# homeboard22.net
KiCad netlist of a schematic drawn in EAGLE
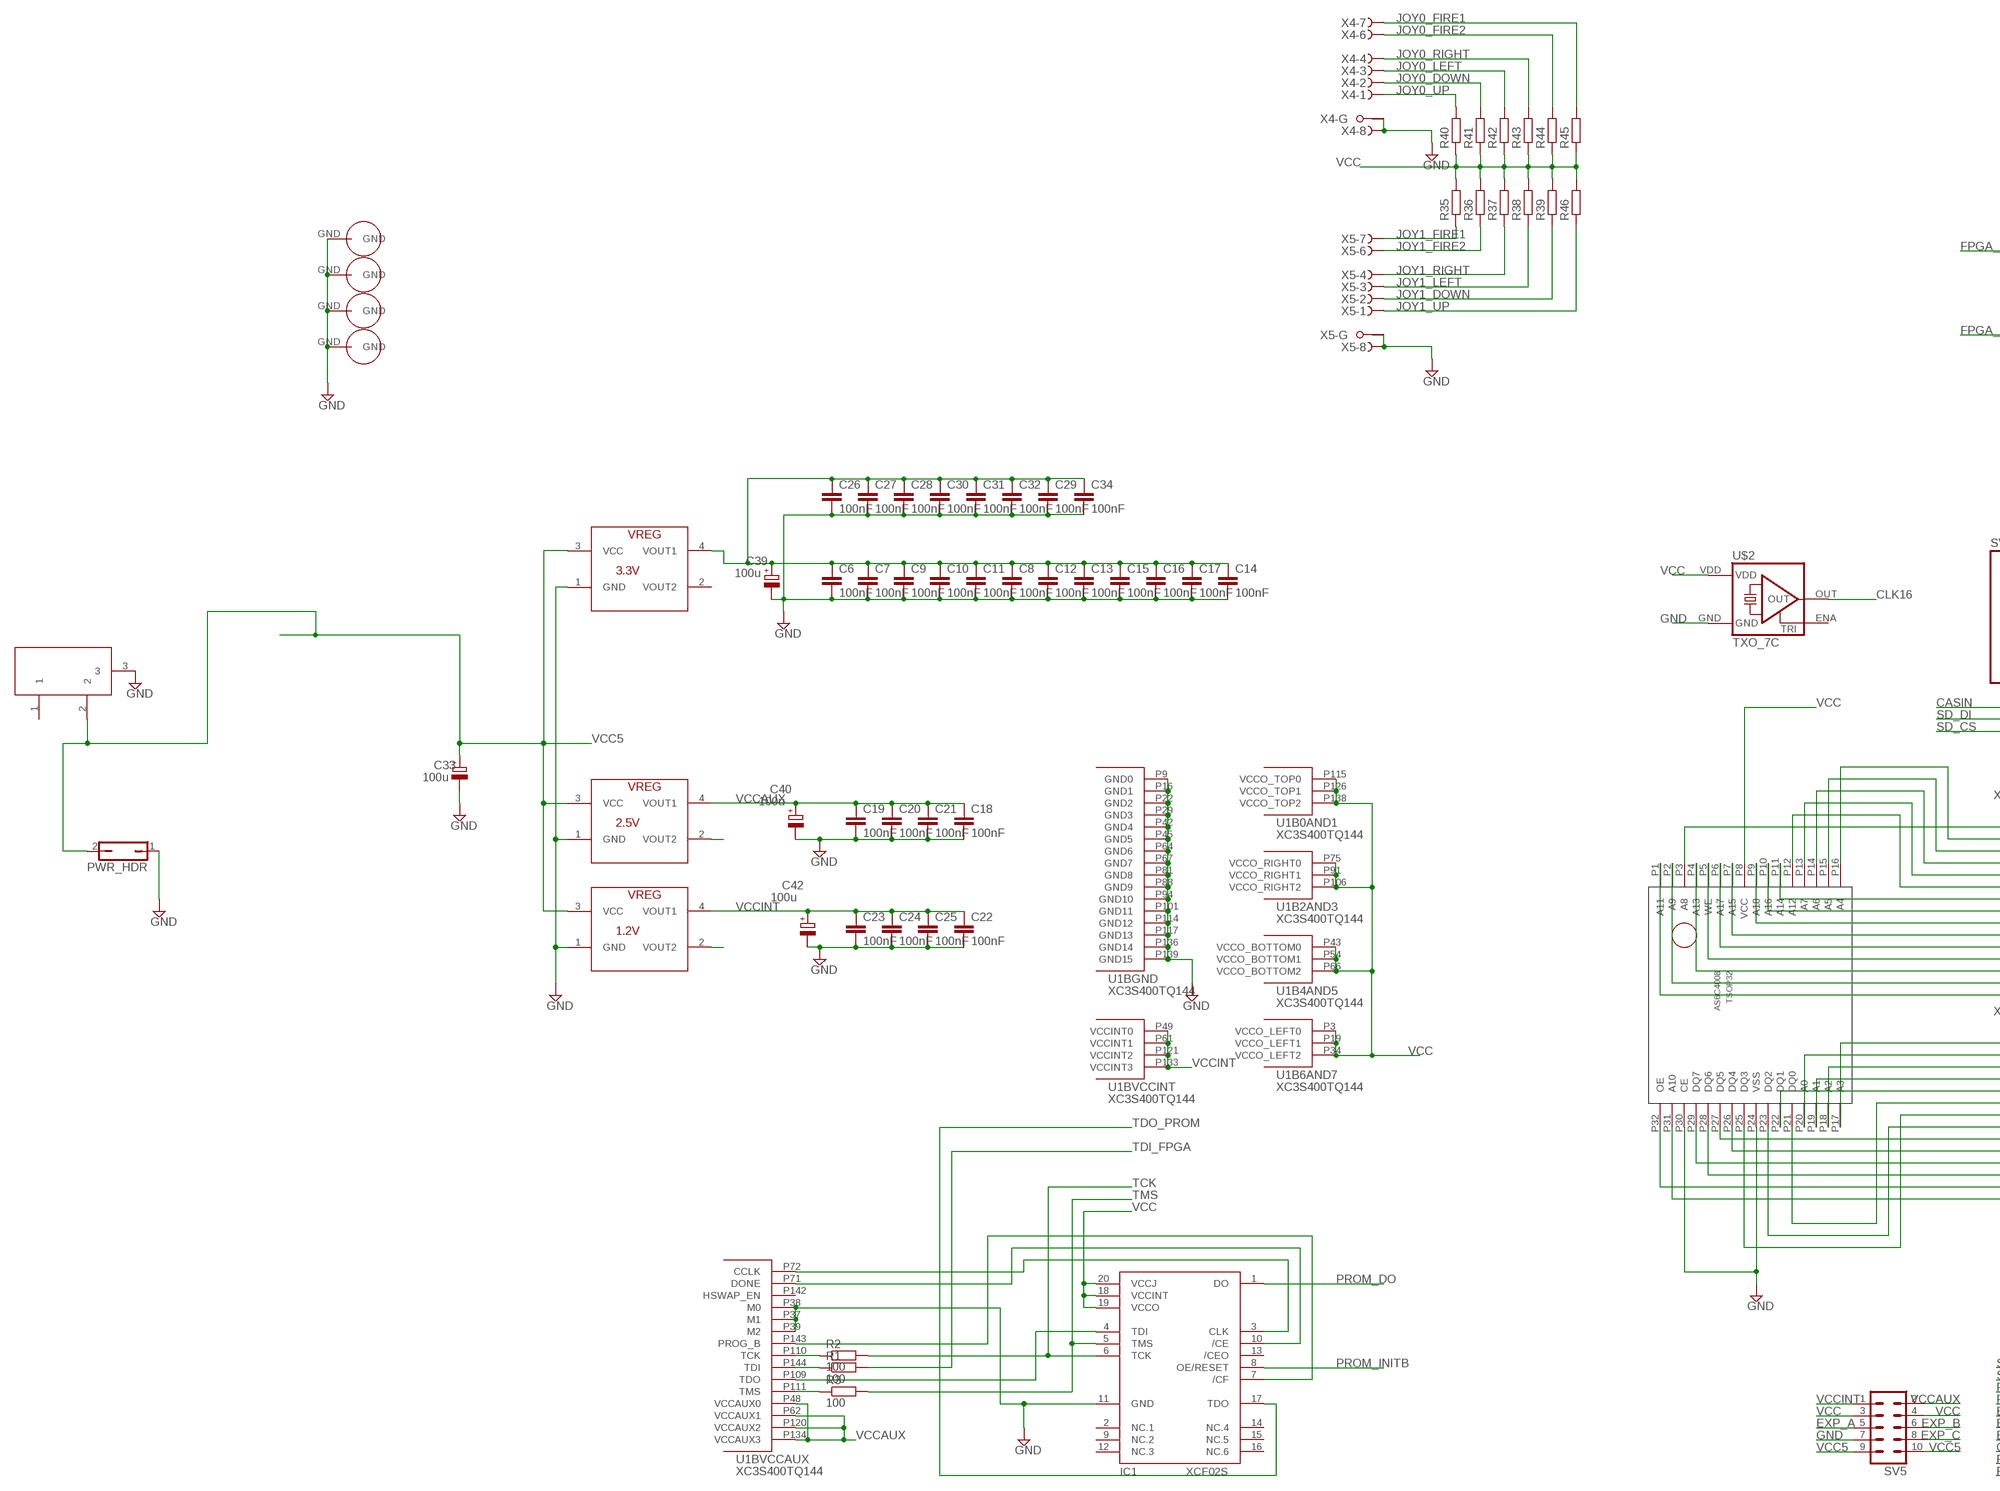
[diagram p0: schematic, sheet 1, part 1 of 3]
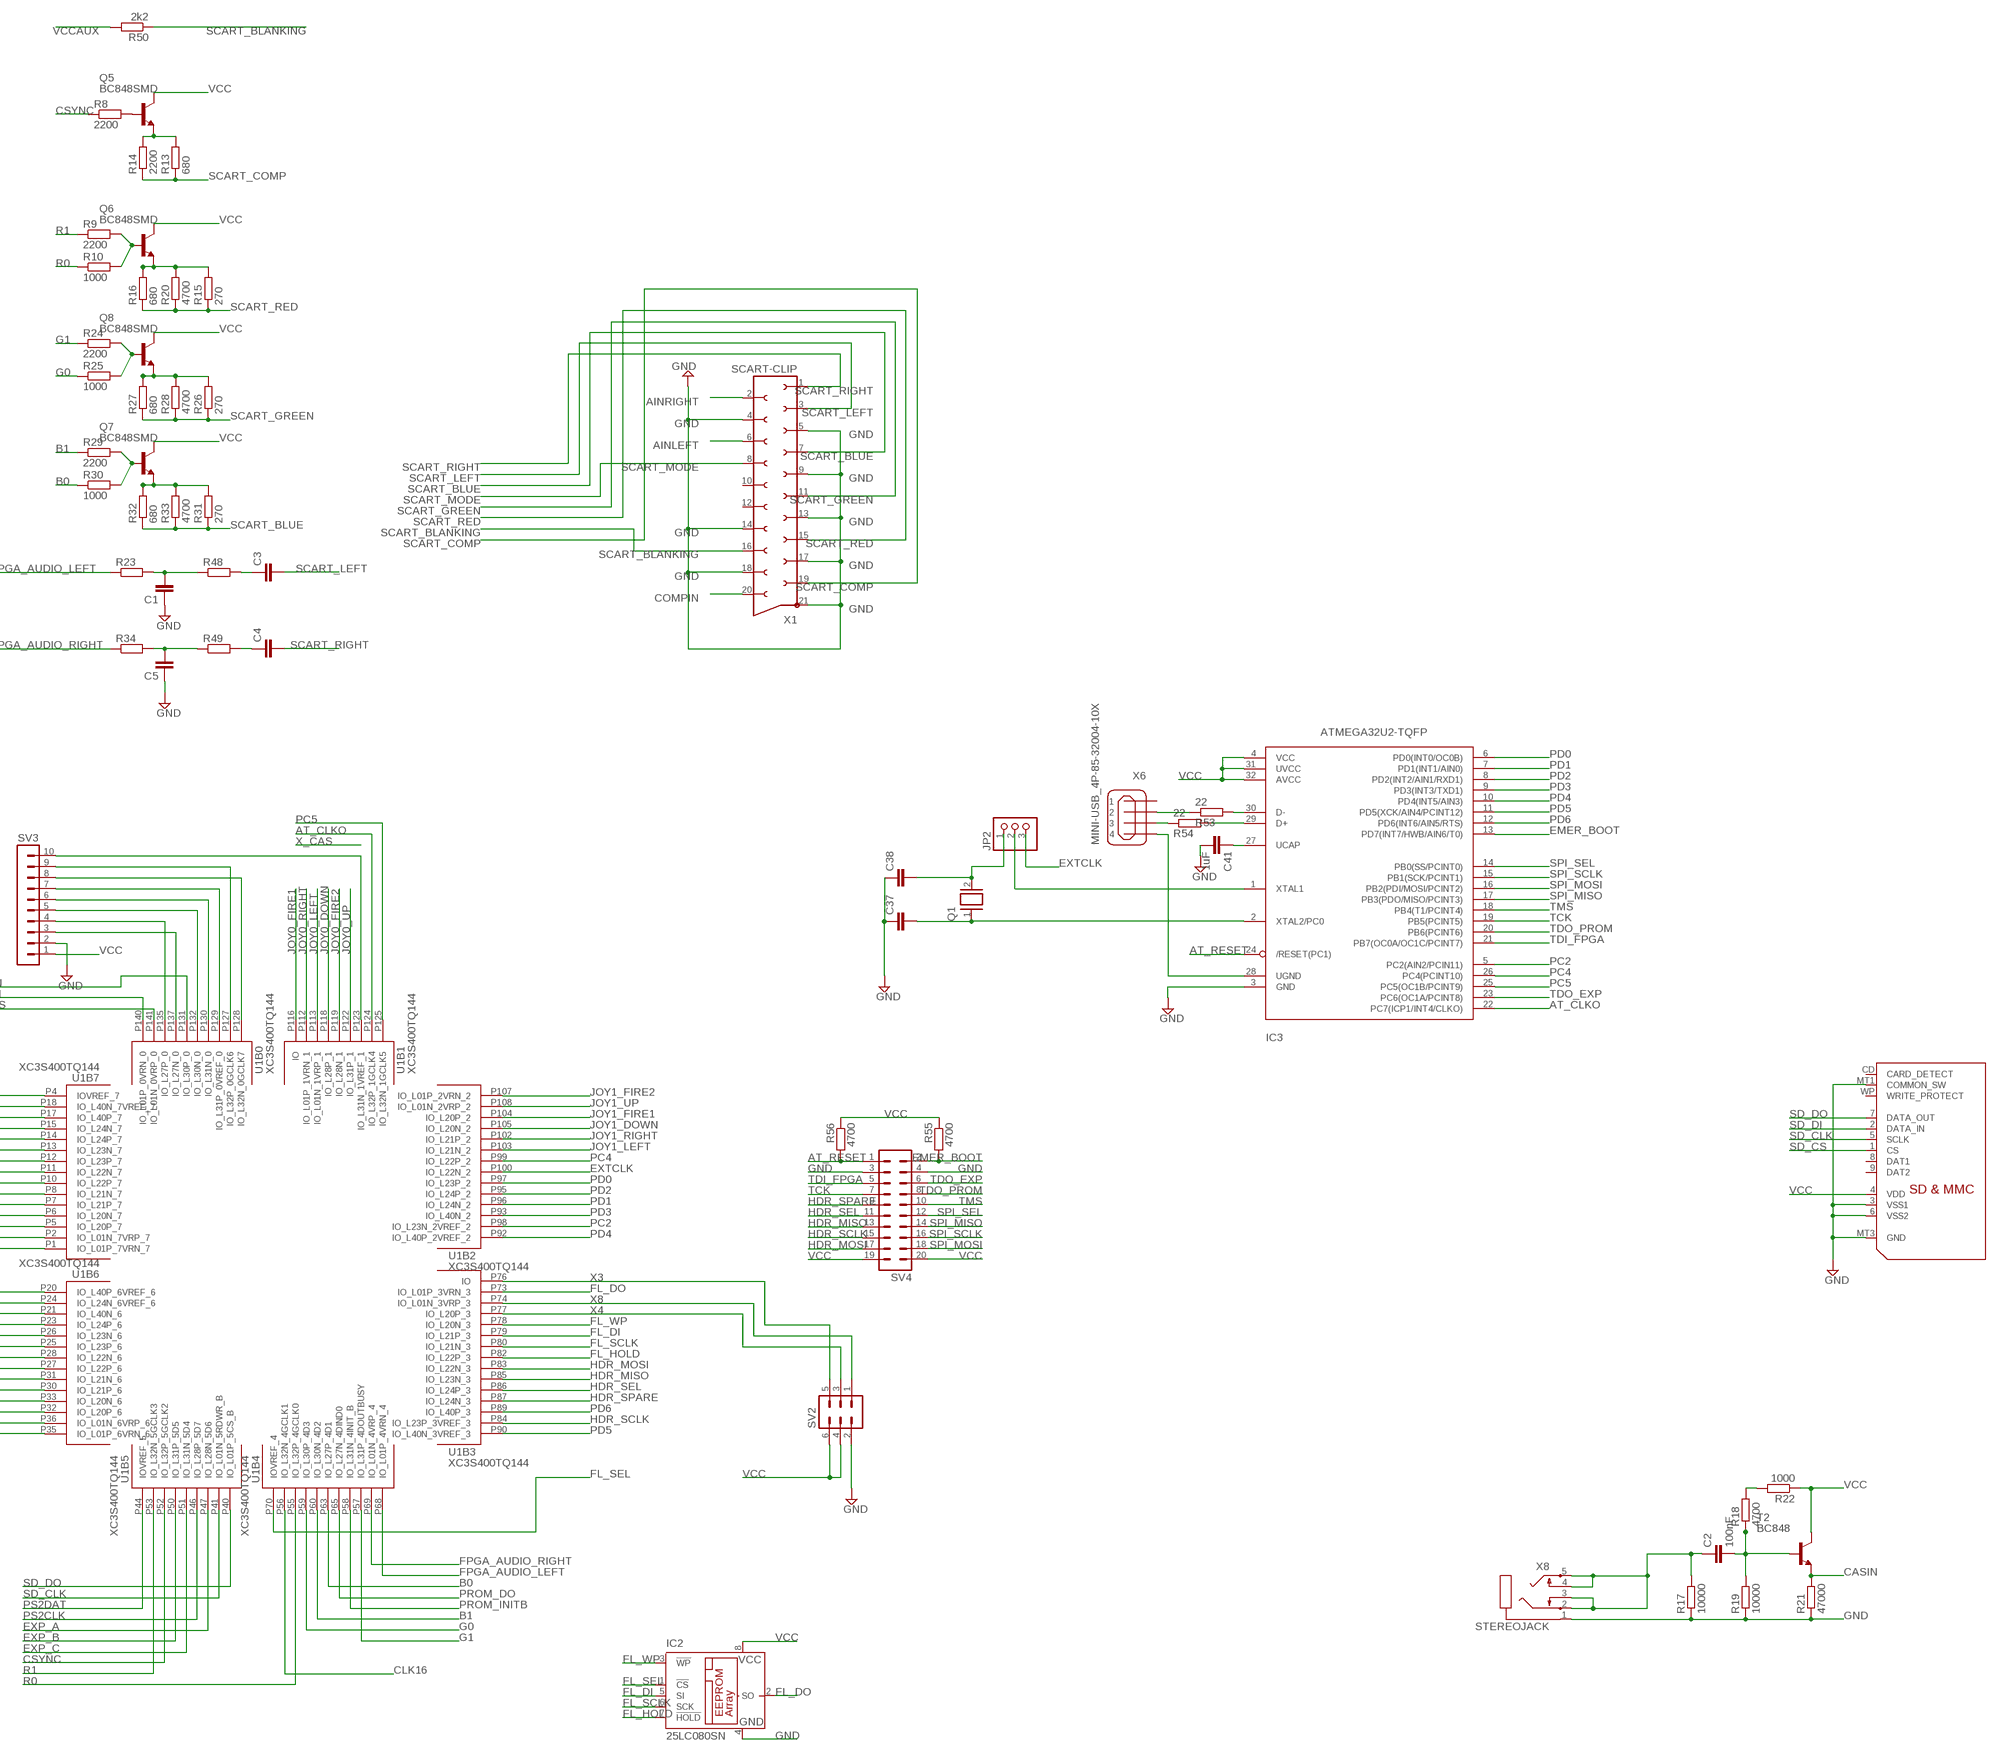
[diagram p1: schematic, sheet 1, part 2 of 3]
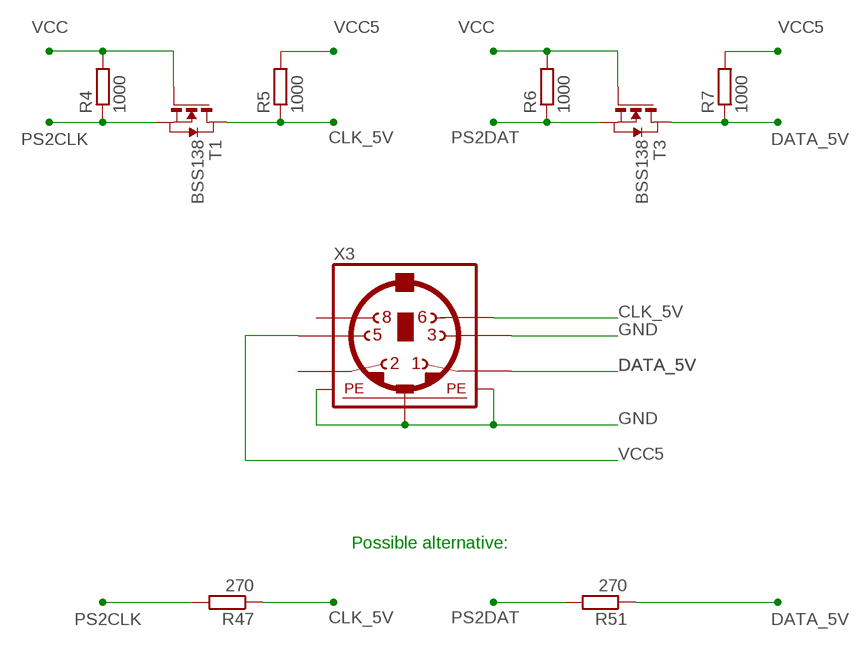
[diagram p2: schematic, sheet 1, part 3 of 3]

(export (version "E")
  (design (tool "Eeschema 10.0.6"))
  (components
    (comp (ref "C1")
      (value "C-EUC0603")
      (footprint "eagle-import:C0603")
      (libsource (lib "eagle-import") (part "resistor_C-EUC0603"))
    )
    (comp (ref "C2")
      (value "100nF")
      (footprint "eagle-import:C0603")
      (libsource (lib "eagle-import") (part "resistor_C-EUC0603"))
    )
    (comp (ref "C3")
      (value "C-EUC0603")
      (footprint "eagle-import:C0603")
      (libsource (lib "eagle-import") (part "resistor_C-EUC0603"))
    )
    (comp (ref "C4")
      (value "C-EUC0603")
      (footprint "eagle-import:C0603")
      (libsource (lib "eagle-import") (part "resistor_C-EUC0603"))
    )
    (comp (ref "C5")
      (value "C-EUC0603")
      (footprint "eagle-import:C0603")
      (libsource (lib "eagle-import") (part "resistor_C-EUC0603"))
    )
    (comp (ref "C6")
      (value "100nF")
      (footprint "eagle-import:C0603")
      (libsource (lib "eagle-import") (part "C-EUC0603"))
    )
    (comp (ref "C7")
      (value "100nF")
      (footprint "eagle-import:C0603")
      (libsource (lib "eagle-import") (part "C-EUC0603"))
    )
    (comp (ref "C8")
      (value "100nF")
      (footprint "eagle-import:C0603")
      (libsource (lib "eagle-import") (part "C-EUC0603"))
    )
    (comp (ref "C9")
      (value "100nF")
      (footprint "eagle-import:C0603")
      (libsource (lib "eagle-import") (part "C-EUC0603"))
    )
    (comp (ref "C10")
      (value "100nF")
      (footprint "eagle-import:C0603")
      (libsource (lib "eagle-import") (part "C-EUC0603"))
    )
    (comp (ref "C11")
      (value "100nF")
      (footprint "eagle-import:C0603")
      (libsource (lib "eagle-import") (part "C-EUC0603"))
    )
    (comp (ref "C12")
      (value "100nF")
      (footprint "eagle-import:C0603")
      (libsource (lib "eagle-import") (part "C-EUC0603"))
    )
    (comp (ref "C13")
      (value "100nF")
      (footprint "eagle-import:C0603")
      (libsource (lib "eagle-import") (part "C-EUC0603"))
    )
    (comp (ref "C14")
      (value "100nF")
      (footprint "eagle-import:C0603")
      (libsource (lib "eagle-import") (part "C-EUC0603"))
    )
    (comp (ref "C15")
      (value "100nF")
      (footprint "eagle-import:C0603")
      (libsource (lib "eagle-import") (part "C-EUC0603"))
    )
    (comp (ref "C16")
      (value "100nF")
      (footprint "eagle-import:C0603")
      (libsource (lib "eagle-import") (part "C-EUC0603"))
    )
    (comp (ref "C17")
      (value "100nF")
      (footprint "eagle-import:C0603")
      (libsource (lib "eagle-import") (part "C-EUC0603"))
    )
    (comp (ref "C18")
      (value "100nF")
      (footprint "eagle-import:C0603")
      (libsource (lib "eagle-import") (part "C-EUC0603"))
    )
    (comp (ref "C19")
      (value "100nF")
      (footprint "eagle-import:C0603")
      (libsource (lib "eagle-import") (part "C-EUC0603"))
    )
    (comp (ref "C20")
      (value "100nF")
      (footprint "eagle-import:C0603")
      (libsource (lib "eagle-import") (part "C-EUC0603"))
    )
    (comp (ref "C21")
      (value "100nF")
      (footprint "eagle-import:C0603")
      (libsource (lib "eagle-import") (part "C-EUC0603"))
    )
    (comp (ref "C22")
      (value "100nF")
      (footprint "eagle-import:C0603")
      (libsource (lib "eagle-import") (part "C-EUC0603"))
    )
    (comp (ref "C23")
      (value "100nF")
      (footprint "eagle-import:C0603")
      (libsource (lib "eagle-import") (part "C-EUC0603"))
    )
    (comp (ref "C24")
      (value "100nF")
      (footprint "eagle-import:C0603")
      (libsource (lib "eagle-import") (part "C-EUC0603"))
    )
    (comp (ref "C25")
      (value "100nF")
      (footprint "eagle-import:C0603")
      (libsource (lib "eagle-import") (part "C-EUC0603"))
    )
    (comp (ref "C26")
      (value "100nF")
      (footprint "eagle-import:C0603")
      (libsource (lib "eagle-import") (part "C-EUC0603"))
    )
    (comp (ref "C27")
      (value "100nF")
      (footprint "eagle-import:C0603")
      (libsource (lib "eagle-import") (part "C-EUC0603"))
    )
    (comp (ref "C28")
      (value "100nF")
      (footprint "eagle-import:C0603")
      (libsource (lib "eagle-import") (part "C-EUC0603"))
    )
    (comp (ref "C29")
      (value "100nF")
      (footprint "eagle-import:C0603")
      (libsource (lib "eagle-import") (part "C-EUC0603"))
    )
    (comp (ref "C30")
      (value "100nF")
      (footprint "eagle-import:C0603")
      (libsource (lib "eagle-import") (part "C-EUC0603"))
    )
    (comp (ref "C31")
      (value "100nF")
      (footprint "eagle-import:C0603")
      (libsource (lib "eagle-import") (part "C-EUC0603"))
    )
    (comp (ref "C32")
      (value "100nF")
      (footprint "eagle-import:C0603")
      (libsource (lib "eagle-import") (part "C-EUC0603"))
    )
    (comp (ref "C33")
      (value "100u")
      (footprint "eagle-import:PANASONIC_D")
      (libsource (lib "eagle-import") (part "CPOL-EUD"))
    )
    (comp (ref "C34")
      (value "100nF")
      (footprint "eagle-import:C0603")
      (libsource (lib "eagle-import") (part "C-EUC0603"))
    )
    (comp (ref "C37")
      (value "C-EUC0805")
      (footprint "eagle-import:C0805")
      (libsource (lib "eagle-import") (part "C-EUC0805"))
    )
    (comp (ref "C38")
      (value "C-EUC0805")
      (footprint "eagle-import:C0805")
      (libsource (lib "eagle-import") (part "C-EUC0805"))
    )
    (comp (ref "C39")
      (value "100u")
      (footprint "eagle-import:PANASONIC_D")
      (libsource (lib "eagle-import") (part "CPOL-EUD"))
    )
    (comp (ref "C40")
      (value "100u")
      (footprint "eagle-import:PANASONIC_D")
      (libsource (lib "eagle-import") (part "CPOL-EUD"))
    )
    (comp (ref "C41")
      (value "1uF")
      (footprint "eagle-import:C0805")
      (libsource (lib "eagle-import") (part "C-EUC0805"))
    )
    (comp (ref "C42")
      (value "100u")
      (footprint "eagle-import:PANASONIC_D")
      (libsource (lib "eagle-import") (part "CPOL-EUD"))
    )
    (comp (ref "IC1")
      (value "XCF02S")
      (footprint "eagle-import:VO20")
      (libsource (lib "eagle-import") (part "XCF02S"))
    )
    (comp (ref "IC2")
      (value "25LC080SN")
      (footprint "eagle-import:SO-08")
      (fields (field (name "MF") "MICROCHIP") (field (name "MPN") "25LC080/SN"))
      (libsource (lib "eagle-import") (part "25SNLC080"))
    )
    (comp (ref "IC3")
      (value "ATMEGA32U2-TQFP")
      (footprint "eagle-import:TQFP32-08")
      (libsource (lib "eagle-import") (part "ATMEGA32U2-TQFP"))
    )
    (comp (ref "JP2")
      (value "PINHD-1X3")
      (footprint "eagle-import:1X03")
      (libsource (lib "eagle-import") (part "PINHD-1X3"))
    )
    (comp (ref "PWR_HDR")
      (value "JP1Q")
      (footprint "eagle-import:JP1")
      (libsource (lib "eagle-import") (part "JP1Q"))
    )
    (comp (ref "Q1")
      (value "XTAL/S")
      (footprint "eagle-import:QS")
      (libsource (lib "eagle-import") (part "XTAL/S"))
    )
    (comp (ref "Q5")
      (value "BC848SMD")
      (footprint "eagle-import:SOT23")
      (libsource (lib "eagle-import") (part "BC848SMD"))
    )
    (comp (ref "Q6")
      (value "BC848SMD")
      (footprint "eagle-import:SOT23")
      (libsource (lib "eagle-import") (part "BC848SMD"))
    )
    (comp (ref "Q7")
      (value "BC848SMD")
      (footprint "eagle-import:SOT23")
      (libsource (lib "eagle-import") (part "BC848SMD"))
    )
    (comp (ref "Q8")
      (value "BC848SMD")
      (footprint "eagle-import:SOT23")
      (libsource (lib "eagle-import") (part "BC848SMD"))
    )
    (comp (ref "R1")
      (value "100")
      (footprint "eagle-import:R0805")
      (libsource (lib "eagle-import") (part "R-EU_R0805"))
    )
    (comp (ref "R2")
      (value "100")
      (footprint "eagle-import:R0805")
      (libsource (lib "eagle-import") (part "R-EU_R0805"))
    )
    (comp (ref "R3")
      (value "100")
      (footprint "eagle-import:R0805")
      (libsource (lib "eagle-import") (part "R-EU_R0805"))
    )
    (comp (ref "R4")
      (value "1000")
      (footprint "eagle-import:R0805")
      (libsource (lib "eagle-import") (part "R-EU_R0805"))
    )
    (comp (ref "R5")
      (value "1000")
      (footprint "eagle-import:R0805")
      (libsource (lib "eagle-import") (part "R-EU_R0805"))
    )
    (comp (ref "R6")
      (value "1000")
      (footprint "eagle-import:R0805")
      (libsource (lib "eagle-import") (part "R-EU_R0805"))
    )
    (comp (ref "R7")
      (value "1000")
      (footprint "eagle-import:R0805")
      (libsource (lib "eagle-import") (part "R-EU_R0805"))
    )
    (comp (ref "R8")
      (value "2200")
      (footprint "eagle-import:R0805")
      (libsource (lib "eagle-import") (part "R-EU_R0805"))
    )
    (comp (ref "R9")
      (value "2200")
      (footprint "eagle-import:R0805")
      (libsource (lib "eagle-import") (part "R-EU_R0805"))
    )
    (comp (ref "R10")
      (value "1000")
      (footprint "eagle-import:R0805")
      (libsource (lib "eagle-import") (part "R-EU_R0805"))
    )
    (comp (ref "R13")
      (value "680")
      (footprint "eagle-import:R0805")
      (libsource (lib "eagle-import") (part "R-EU_R0805"))
    )
    (comp (ref "R14")
      (value "2200")
      (footprint "eagle-import:R0805")
      (libsource (lib "eagle-import") (part "R-EU_R0805"))
    )
    (comp (ref "R15")
      (value "270")
      (footprint "eagle-import:R0805")
      (libsource (lib "eagle-import") (part "R-EU_R0805"))
    )
    (comp (ref "R16")
      (value "680")
      (footprint "eagle-import:R0805")
      (libsource (lib "eagle-import") (part "R-EU_R0805"))
    )
    (comp (ref "R17")
      (value "10000")
      (footprint "eagle-import:R0805")
      (libsource (lib "eagle-import") (part "R-EU_R0805"))
    )
    (comp (ref "R18")
      (value "4700")
      (footprint "eagle-import:R0805")
      (libsource (lib "eagle-import") (part "R-EU_R0805"))
    )
    (comp (ref "R19")
      (value "10000")
      (footprint "eagle-import:R0805")
      (libsource (lib "eagle-import") (part "R-EU_R0805"))
    )
    (comp (ref "R20")
      (value "4700")
      (footprint "eagle-import:R0805")
      (libsource (lib "eagle-import") (part "R-EU_R0805"))
    )
    (comp (ref "R21")
      (value "47000")
      (footprint "eagle-import:R0805")
      (libsource (lib "eagle-import") (part "R-EU_R0805"))
    )
    (comp (ref "R22")
      (value "1000")
      (footprint "eagle-import:R0805")
      (libsource (lib "eagle-import") (part "R-EU_R0805"))
    )
    (comp (ref "R23")
      (value "R-EU_M0805")
      (footprint "eagle-import:M0805")
      (libsource (lib "eagle-import") (part "resistor_R-EU_M0805"))
    )
    (comp (ref "R24")
      (value "2200")
      (footprint "eagle-import:R0805")
      (libsource (lib "eagle-import") (part "R-EU_R0805"))
    )
    (comp (ref "R25")
      (value "1000")
      (footprint "eagle-import:R0805")
      (libsource (lib "eagle-import") (part "R-EU_R0805"))
    )
    (comp (ref "R26")
      (value "270")
      (footprint "eagle-import:R0805")
      (libsource (lib "eagle-import") (part "R-EU_R0805"))
    )
    (comp (ref "R27")
      (value "680")
      (footprint "eagle-import:R0805")
      (libsource (lib "eagle-import") (part "R-EU_R0805"))
    )
    (comp (ref "R28")
      (value "4700")
      (footprint "eagle-import:R0805")
      (libsource (lib "eagle-import") (part "R-EU_R0805"))
    )
    (comp (ref "R29")
      (value "2200")
      (footprint "eagle-import:R0805")
      (libsource (lib "eagle-import") (part "R-EU_R0805"))
    )
    (comp (ref "R30")
      (value "1000")
      (footprint "eagle-import:R0805")
      (libsource (lib "eagle-import") (part "R-EU_R0805"))
    )
    (comp (ref "R31")
      (value "270")
      (footprint "eagle-import:R0805")
      (libsource (lib "eagle-import") (part "R-EU_R0805"))
    )
    (comp (ref "R32")
      (value "680")
      (footprint "eagle-import:R0805")
      (libsource (lib "eagle-import") (part "R-EU_R0805"))
    )
    (comp (ref "R33")
      (value "4700")
      (footprint "eagle-import:R0805")
      (libsource (lib "eagle-import") (part "R-EU_R0805"))
    )
    (comp (ref "R34")
      (value "R-EU_M0805")
      (footprint "eagle-import:M0805")
      (libsource (lib "eagle-import") (part "resistor_R-EU_M0805"))
    )
    (comp (ref "R35")
      (value "R-EU_M0805")
      (footprint "eagle-import:M0805")
      (libsource (lib "eagle-import") (part "resistor_R-EU_M0805"))
    )
    (comp (ref "R36")
      (value "R-EU_M0805")
      (footprint "eagle-import:M0805")
      (libsource (lib "eagle-import") (part "resistor_R-EU_M0805"))
    )
    (comp (ref "R37")
      (value "R-EU_M0805")
      (footprint "eagle-import:M0805")
      (libsource (lib "eagle-import") (part "resistor_R-EU_M0805"))
    )
    (comp (ref "R38")
      (value "R-EU_M0805")
      (footprint "eagle-import:M0805")
      (libsource (lib "eagle-import") (part "resistor_R-EU_M0805"))
    )
    (comp (ref "R39")
      (value "R-EU_M0805")
      (footprint "eagle-import:M0805")
      (libsource (lib "eagle-import") (part "resistor_R-EU_M0805"))
    )
    (comp (ref "R40")
      (value "R-EU_M0805")
      (footprint "eagle-import:M0805")
      (libsource (lib "eagle-import") (part "resistor_R-EU_M0805"))
    )
    (comp (ref "R41")
      (value "R-EU_M0805")
      (footprint "eagle-import:M0805")
      (libsource (lib "eagle-import") (part "resistor_R-EU_M0805"))
    )
    (comp (ref "R42")
      (value "R-EU_M0805")
      (footprint "eagle-import:M0805")
      (libsource (lib "eagle-import") (part "resistor_R-EU_M0805"))
    )
    (comp (ref "R43")
      (value "R-EU_M0805")
      (footprint "eagle-import:M0805")
      (libsource (lib "eagle-import") (part "resistor_R-EU_M0805"))
    )
    (comp (ref "R44")
      (value "R-EU_M0805")
      (footprint "eagle-import:M0805")
      (libsource (lib "eagle-import") (part "resistor_R-EU_M0805"))
    )
    (comp (ref "R45")
      (value "R-EU_M0805")
      (footprint "eagle-import:M0805")
      (libsource (lib "eagle-import") (part "resistor_R-EU_M0805"))
    )
    (comp (ref "R46")
      (value "R-EU_M0805")
      (footprint "eagle-import:M0805")
      (libsource (lib "eagle-import") (part "resistor_R-EU_M0805"))
    )
    (comp (ref "R47")
      (value "270")
      (footprint "eagle-import:R0805")
      (libsource (lib "eagle-import") (part "R-EU_R0805"))
    )
    (comp (ref "R48")
      (value "R-EU_M0805")
      (footprint "eagle-import:M0805")
      (libsource (lib "eagle-import") (part "resistor_R-EU_M0805"))
    )
    (comp (ref "R49")
      (value "R-EU_M0805")
      (footprint "eagle-import:M0805")
      (libsource (lib "eagle-import") (part "resistor_R-EU_M0805"))
    )
    (comp (ref "R50")
      (value "2k2")
      (footprint "eagle-import:M0805")
      (libsource (lib "eagle-import") (part "resistor_R-EU_M0805"))
    )
    (comp (ref "R51")
      (value "270")
      (footprint "eagle-import:R0805")
      (libsource (lib "eagle-import") (part "R-EU_R0805"))
    )
    (comp (ref "R53")
      (value "22")
      (footprint "eagle-import:R0805")
      (libsource (lib "eagle-import") (part "R-EU_R0805"))
    )
    (comp (ref "R54")
      (value "22")
      (footprint "eagle-import:R0805")
      (libsource (lib "eagle-import") (part "R-EU_R0805"))
    )
    (comp (ref "R55")
      (value "4700")
      (footprint "eagle-import:R0805")
      (libsource (lib "eagle-import") (part "R-EU_R0805"))
    )
    (comp (ref "R56")
      (value "4700")
      (footprint "eagle-import:R0805")
      (libsource (lib "eagle-import") (part "R-EU_R0805"))
    )
    (comp (ref "REG1.2")
      (value "1.2V")
      (footprint "eagle-import:SOT223")
      (libsource (lib "eagle-import") (part "NX1117"))
    )
    (comp (ref "REG2.5")
      (value "2.5V")
      (footprint "eagle-import:SOT223")
      (libsource (lib "eagle-import") (part "NX1117"))
    )
    (comp (ref "SV2")
      (value "MA03-2")
      (footprint "eagle-import:MA03-2")
      (libsource (lib "eagle-import") (part "MA03-2"))
    )
    (comp (ref "SV3")
      (value "MA10-1")
      (footprint "eagle-import:MA10-1")
      (libsource (lib "eagle-import") (part "MA10-1"))
    )
    (comp (ref "SV4")
      (value "MA10-2")
      (footprint "eagle-import:MA10-2")
      (libsource (lib "eagle-import") (part "MA10-2"))
    )
    (comp (ref "SV5")
      (value "MA05-2")
      (footprint "eagle-import:MA05-2")
      (libsource (lib "eagle-import") (part "MA05-2"))
    )
    (comp (ref "T1")
      (value "BSS138")
      (footprint "eagle-import:SOT-23")
      (libsource (lib "eagle-import") (part "NMOSSOT23"))
    )
    (comp (ref "T2")
      (value "BC848")
      (footprint "eagle-import:SOT23")
      (libsource (lib "eagle-import") (part "BC848"))
    )
    (comp (ref "T3")
      (value "BSS138")
      (footprint "eagle-import:SOT-23")
      (libsource (lib "eagle-import") (part "NMOSSOT23"))
    )
    (comp (ref "U$1")
      (value "GNDHOLE")
      (footprint "eagle-import:GNDHOLE")
      (libsource (lib "eagle-import") (part "GNDHOLE"))
    )
    (comp (ref "U$2")
      (value "TXO_7C")
      (footprint "eagle-import:OSC_7C")
      (libsource (lib "eagle-import") (part "TXO_7C"))
    )
    (comp (ref "U$3")
      (value "SDMMCNOHOLE")
      (footprint "eagle-import:SDCARD-NOHOLE")
      (libsource (lib "eagle-import") (part "SDMMCNOHOLE"))
    )
    (comp (ref "U$4")
      (value "3.3V")
      (footprint "eagle-import:SOT223")
      (libsource (lib "eagle-import") (part "NX1117"))
    )
    (comp (ref "U$6")
      (value "AS6C4008")
      (footprint "eagle-import:TSOP32")
      (libsource (lib "eagle-import") (part "AS6C4008"))
    )
    (comp (ref "U$7")
      (value "GNDHOLE")
      (footprint "eagle-import:GNDHOLE")
      (libsource (lib "eagle-import") (part "GNDHOLE"))
    )
    (comp (ref "U$8")
      (value "GNDHOLE")
      (footprint "eagle-import:GNDHOLE")
      (libsource (lib "eagle-import") (part "GNDHOLE"))
    )
    (comp (ref "U$9")
      (value "GNDHOLE")
      (footprint "eagle-import:GNDHOLE")
      (libsource (lib "eagle-import") (part "GNDHOLE"))
    )
    (comp (ref "U1")
      (value "XC3S400TQ144")
      (footprint "eagle-import:TQ144")
      (libsource (lib "eagle-import") (part "XC3S400TQ144"))
    )
    (comp (ref "X1")
      (value "SCART-CLIP")
      (footprint "eagle-import:SCART-CLIP")
      (libsource (lib "eagle-import") (part "SCART-CLIP"))
    )
    (comp (ref "X3")
      (value "MINI_DIN_6")
      (footprint "eagle-import:M_DIN6")
      (libsource (lib "eagle-import") (part "MINI_DIN_6"))
    )
    (comp (ref "X4")
      (value "F09HPS")
      (footprint "eagle-import:F09HP")
      (libsource (lib "eagle-import") (part "F09HPS"))
    )
    (comp (ref "X5")
      (value "F09HPS")
      (footprint "eagle-import:F09HP")
      (libsource (lib "eagle-import") (part "F09HPS"))
    )
    (comp (ref "X6")
      (value "MINI-USB_4P-85-32004-10X")
      (footprint "eagle-import:85-32004-10X")
      (libsource (lib "eagle-import") (part "MINI-USB_4P-85-32004-10X"))
    )
    (comp (ref "X7")
      (value "DC21MMX")
      (footprint "eagle-import:DC-21MM")
      (libsource (lib "eagle-import") (part "DC21MMX"))
    )
    (comp (ref "X8")
      (value "STEREOJACK")
      (footprint "eagle-import:20-0137")
      (libsource (lib "eagle-import") (part "STEREOJACK"))
    )
  )
  (nets
    (net (code "1") (name "/1") (class "Default")
      (node (ref "X7") (pin "1") (pinfunction "1_1") (pintype "power_in"))
    )
    (net (code "2") (name "/AINLEFT") (class "Default")
      (node (ref "X1") (pin "6") (pinfunction "6_6") (pintype "passive"))
    )
    (net (code "3") (name "/AINRIGHT") (class "Default")
      (node (ref "X1") (pin "2") (pinfunction "2_2") (pintype "passive"))
    )
    (net (code "4") (name "/AT_CLKO") (class "Default")
      (node (ref "IC3") (pin "22") (pinfunction "PC7(ICP1/INT4/CLKO)_22") (pintype "bidirectional"))
      (node (ref "U1") (pin "P124") (pinfunction "IO_L32P_1GCLK4_P124") (pintype "bidirectional"))
    )
    (net (code "5") (name "/AT_RESET") (class "Default")
      (node (ref "IC3") (pin "24") (pinfunction "/RESET(PC1)_24") (pintype "bidirectional"))
      (node (ref "R56") (pin "2") (pinfunction "2_2") (pintype "passive"))
      (node (ref "SV4") (pin "1") (pinfunction "1_1") (pintype "passive"))
    )
    (net (code "6") (name "/B0") (class "Default")
      (node (ref "R30") (pin "1") (pinfunction "1_1") (pintype "passive"))
      (node (ref "U1") (pin "P63") (pinfunction "IO_L27P_4D1_P63") (pintype "bidirectional"))
    )
    (net (code "7") (name "/B1") (class "Default")
      (node (ref "R29") (pin "1") (pinfunction "1_1") (pintype "passive"))
      (node (ref "U1") (pin "P60") (pinfunction "IO_L30N_4D2_P60") (pintype "bidirectional"))
    )
    (net (code "8") (name "/CASIN") (class "Default")
      (node (ref "R21") (pin "2") (pinfunction "2_2") (pintype "passive"))
      (node (ref "T2") (pin "2") (pinfunction "E_2") (pintype "passive"))
      (node (ref "U1") (pin "P131") (pinfunction "IO_L30P_0_P131") (pintype "bidirectional"))
    )
    (net (code "9") (name "/CLK16") (class "Default")
      (node (ref "U$2") (pin "OUT") (pinfunction "OUT_OUT") (pintype "output"))
      (node (ref "U1") (pin "P56") (pinfunction "IO_L32N_4GCLK1_P56") (pintype "bidirectional"))
    )
    (net (code "10") (name "/CLK_5V") (class "Default")
      (node (ref "R47") (pin "1") (pinfunction "1_1") (pintype "passive"))
      (node (ref "R5") (pin "1") (pinfunction "1_1") (pintype "passive"))
      (node (ref "T1") (pin "1") (pinfunction "D_1") (pintype "passive"))
      (node (ref "X3") (pin "6") (pinfunction "6_6") (pintype "passive"))
    )
    (net (code "11") (name "/COMPIN") (class "Default")
      (node (ref "X1") (pin "20") (pinfunction "20_20") (pintype "passive"))
    )
    (net (code "12") (name "/CSYNC") (class "Default")
      (node (ref "R8") (pin "1") (pinfunction "1_1") (pintype "passive"))
      (node (ref "U1") (pin "P52") (pinfunction "IO_L32P_5GCLK2_P52") (pintype "bidirectional"))
    )
    (net (code "13") (name "/DATA_5V") (class "Default")
      (node (ref "R51") (pin "1") (pinfunction "1_1") (pintype "passive"))
      (node (ref "R7") (pin "1") (pinfunction "1_1") (pintype "passive"))
      (node (ref "T3") (pin "1") (pinfunction "D_1") (pintype "passive"))
      (node (ref "X3") (pin "1") (pinfunction "1_1") (pintype "passive"))
    )
    (net (code "14") (name "/EMER_BOOT") (class "Default")
      (node (ref "IC3") (pin "13") (pinfunction "PD7(INT7/HWB/AIN6/T0)_13") (pintype "bidirectional"))
      (node (ref "R55") (pin "2") (pinfunction "2_2") (pintype "passive"))
      (node (ref "SV4") (pin "2") (pinfunction "2_2") (pintype "passive"))
    )
    (net (code "15") (name "/EXP_A") (class "Default")
      (node (ref "SV5") (pin "5") (pinfunction "5_5") (pintype "passive"))
      (node (ref "U1") (pin "P47") (pinfunction "IO_L28N_5D6_P47") (pintype "bidirectional"))
    )
    (net (code "16") (name "/EXP_B") (class "Default")
      (node (ref "SV5") (pin "6") (pinfunction "6_6") (pintype "passive"))
      (node (ref "U1") (pin "P50") (pinfunction "IO_L31P_5D5_P50") (pintype "bidirectional"))
    )
    (net (code "17") (name "/EXP_C") (class "Default")
      (node (ref "SV5") (pin "8") (pinfunction "8_8") (pintype "passive"))
      (node (ref "U1") (pin "P51") (pinfunction "IO_L31N_5D4_P51") (pintype "bidirectional"))
    )
    (net (code "18") (name "/EXTCLK") (class "Default")
      (node (ref "JP2") (pin "3") (pinfunction "3_3") (pintype "passive"))
      (node (ref "U1") (pin "P100") (pinfunction "IO_L22N_2_P100") (pintype "bidirectional"))
    )
    (net (code "19") (name "/FL_DI") (class "Default")
      (node (ref "IC2") (pin "5") (pinfunction "SI_5") (pintype "input"))
      (node (ref "U1") (pin "P79") (pinfunction "IO_L21P_3_P79") (pintype "bidirectional"))
    )
    (net (code "20") (name "/FL_DO") (class "Default")
      (node (ref "IC2") (pin "2") (pinfunction "SO_2") (pintype "bidirectional"))
      (node (ref "U1") (pin "P73") (pinfunction "IO_L01P_3VRN_3_P73") (pintype "bidirectional"))
    )
    (net (code "21") (name "/FL_HOLD") (class "Default")
      (node (ref "IC2") (pin "7") (pinfunction "~{HOLD}_7") (pintype "input"))
      (node (ref "U1") (pin "P82") (pinfunction "IO_L22P_3_P82") (pintype "bidirectional"))
    )
    (net (code "22") (name "/FL_SCLK") (class "Default")
      (node (ref "IC2") (pin "6") (pinfunction "SCK_6") (pintype "input"))
      (node (ref "U1") (pin "P80") (pinfunction "IO_L21N_3_P80") (pintype "bidirectional"))
    )
    (net (code "23") (name "/FL_SEL") (class "Default")
      (node (ref "IC2") (pin "1") (pinfunction "~{CS}_1") (pintype "input"))
      (node (ref "U1") (pin "P70") (pinfunction "IOVREF_4_P70") (pintype "bidirectional"))
    )
    (net (code "24") (name "/FL_WP") (class "Default")
      (node (ref "IC2") (pin "3") (pinfunction "~{WP}_3") (pintype "input"))
      (node (ref "U1") (pin "P78") (pinfunction "IO_L20N_3_P78") (pintype "bidirectional"))
    )
    (net (code "25") (name "/FPGA_AUDIO_LEFT") (class "Default")
      (node (ref "R23") (pin "1") (pinfunction "1_1") (pintype "passive"))
      (node (ref "U1") (pin "P68") (pinfunction "IO_L01P_4VRN_4_P68") (pintype "bidirectional"))
    )
    (net (code "26") (name "/FPGA_AUDIO_RIGHT") (class "Default")
      (node (ref "R34") (pin "1") (pinfunction "1_1") (pintype "passive"))
      (node (ref "U1") (pin "P69") (pinfunction "IO_L01N_4VRP_4_P69") (pintype "bidirectional"))
    )
    (net (code "27") (name "/G0") (class "Default")
      (node (ref "R25") (pin "1") (pinfunction "1_1") (pintype "passive"))
      (node (ref "U1") (pin "P59") (pinfunction "IO_L30P_4D3_P59") (pintype "bidirectional"))
    )
    (net (code "28") (name "/G1") (class "Default")
      (node (ref "R24") (pin "1") (pinfunction "1_1") (pintype "passive"))
      (node (ref "U1") (pin "P57") (pinfunction "IO_L31P_4DOUTBUSY_P57") (pintype "bidirectional"))
    )
    (net (code "29") (name "/HDR_MISO") (class "Default")
      (node (ref "SV4") (pin "13") (pinfunction "13_13") (pintype "passive"))
      (node (ref "U1") (pin "P85") (pinfunction "IO_L23N_3_P85") (pintype "bidirectional"))
    )
    (net (code "30") (name "/HDR_MOSI") (class "Default")
      (node (ref "SV4") (pin "17") (pinfunction "17_17") (pintype "passive"))
      (node (ref "U1") (pin "P83") (pinfunction "IO_L22N_3_P83") (pintype "bidirectional"))
    )
    (net (code "31") (name "/HDR_SCLK") (class "Default")
      (node (ref "SV4") (pin "15") (pinfunction "15_15") (pintype "passive"))
      (node (ref "U1") (pin "P84") (pinfunction "IO_L23P_3VREF_3_P84") (pintype "bidirectional"))
    )
    (net (code "32") (name "/HDR_SEL") (class "Default")
      (node (ref "SV4") (pin "11") (pinfunction "11_11") (pintype "passive"))
      (node (ref "U1") (pin "P86") (pinfunction "IO_L24P_3_P86") (pintype "bidirectional"))
    )
    (net (code "33") (name "/HDR_SPARE") (class "Default")
      (node (ref "SV4") (pin "9") (pinfunction "9_9") (pintype "passive"))
      (node (ref "U1") (pin "P87") (pinfunction "IO_L24N_3_P87") (pintype "bidirectional"))
    )
    (net (code "34") (name "/JOY0_DOWN") (class "Default")
      (node (ref "R41") (pin "2") (pinfunction "2_2") (pintype "passive"))
      (node (ref "U1") (pin "P118") (pinfunction "IO_L28P_1_P118") (pintype "bidirectional"))
      (node (ref "X4") (pin "2") (pinfunction "F_2") (pintype "passive"))
    )
    (net (code "35") (name "/JOY0_FIRE1") (class "Default")
      (node (ref "R45") (pin "2") (pinfunction "2_2") (pintype "passive"))
      (node (ref "U1") (pin "P116") (pinfunction "IO_P116") (pintype "bidirectional"))
      (node (ref "X4") (pin "7") (pinfunction "F_7") (pintype "passive"))
    )
    (net (code "36") (name "/JOY0_FIRE2") (class "Default")
      (node (ref "R44") (pin "2") (pinfunction "2_2") (pintype "passive"))
      (node (ref "U1") (pin "P119") (pinfunction "IO_L28N_1_P119") (pintype "bidirectional"))
      (node (ref "X4") (pin "6") (pinfunction "F_6") (pintype "passive"))
    )
    (net (code "37") (name "/JOY0_LEFT") (class "Default")
      (node (ref "R42") (pin "2") (pinfunction "2_2") (pintype "passive"))
      (node (ref "U1") (pin "P113") (pinfunction "IO_L01N_1VRP_1_P113") (pintype "bidirectional"))
      (node (ref "X4") (pin "3") (pinfunction "F_3") (pintype "passive"))
    )
    (net (code "38") (name "/JOY0_RIGHT") (class "Default")
      (node (ref "R43") (pin "2") (pinfunction "2_2") (pintype "passive"))
      (node (ref "U1") (pin "P112") (pinfunction "IO_L01P_1VRN_1_P112") (pintype "bidirectional"))
      (node (ref "X4") (pin "4") (pinfunction "F_4") (pintype "passive"))
    )
    (net (code "39") (name "/JOY0_UP") (class "Default")
      (node (ref "R40") (pin "2") (pinfunction "2_2") (pintype "passive"))
      (node (ref "U1") (pin "P122") (pinfunction "IO_L31P_1_P122") (pintype "bidirectional"))
      (node (ref "X4") (pin "1") (pinfunction "F_1") (pintype "passive"))
    )
    (net (code "40") (name "/JOY1_DOWN") (class "Default")
      (node (ref "R39") (pin "1") (pinfunction "1_1") (pintype "passive"))
      (node (ref "U1") (pin "P105") (pinfunction "IO_L20N_2_P105") (pintype "bidirectional"))
      (node (ref "X5") (pin "2") (pinfunction "F_2") (pintype "passive"))
    )
    (net (code "41") (name "/JOY1_FIRE1") (class "Default")
      (node (ref "R35") (pin "1") (pinfunction "1_1") (pintype "passive"))
      (node (ref "U1") (pin "P104") (pinfunction "IO_L20P_2_P104") (pintype "bidirectional"))
      (node (ref "X5") (pin "7") (pinfunction "F_7") (pintype "passive"))
    )
    (net (code "42") (name "/JOY1_FIRE2") (class "Default")
      (node (ref "R36") (pin "1") (pinfunction "1_1") (pintype "passive"))
      (node (ref "U1") (pin "P107") (pinfunction "IO_L01P_2VRN_2_P107") (pintype "bidirectional"))
      (node (ref "X5") (pin "6") (pinfunction "F_6") (pintype "passive"))
    )
    (net (code "43") (name "/JOY1_LEFT") (class "Default")
      (node (ref "R38") (pin "1") (pinfunction "1_1") (pintype "passive"))
      (node (ref "U1") (pin "P103") (pinfunction "IO_L21N_2_P103") (pintype "bidirectional"))
      (node (ref "X5") (pin "3") (pinfunction "F_3") (pintype "passive"))
    )
    (net (code "44") (name "/JOY1_RIGHT") (class "Default")
      (node (ref "R37") (pin "1") (pinfunction "1_1") (pintype "passive"))
      (node (ref "U1") (pin "P102") (pinfunction "IO_L21P_2_P102") (pintype "bidirectional"))
      (node (ref "X5") (pin "4") (pinfunction "F_4") (pintype "passive"))
    )
    (net (code "45") (name "/JOY1_UP") (class "Default")
      (node (ref "R46") (pin "1") (pinfunction "1_1") (pintype "passive"))
      (node (ref "U1") (pin "P108") (pinfunction "IO_L01N_2VRP_2_P108") (pintype "bidirectional"))
      (node (ref "X5") (pin "1") (pinfunction "F_1") (pintype "passive"))
    )
    (net (code "46") (name "/PC2") (class "Default")
      (node (ref "IC3") (pin "5") (pinfunction "PC2(AIN2/PCIN11)_5") (pintype "bidirectional"))
      (node (ref "U1") (pin "P98") (pinfunction "IO_L23N_2VREF_2_P98") (pintype "bidirectional"))
    )
    (net (code "47") (name "/PC4") (class "Default")
      (node (ref "IC3") (pin "26") (pinfunction "PC4(PCINT10)_26") (pintype "bidirectional"))
      (node (ref "U1") (pin "P99") (pinfunction "IO_L22P_2_P99") (pintype "bidirectional"))
    )
    (net (code "48") (name "/PC5") (class "Default")
      (node (ref "IC3") (pin "25") (pinfunction "PC5(OC1B/PCINT9)_25") (pintype "bidirectional"))
      (node (ref "U1") (pin "P125") (pinfunction "IO_L32N_1GCLK5_P125") (pintype "bidirectional"))
    )
    (net (code "49") (name "/PD0") (class "Default")
      (node (ref "IC3") (pin "6") (pinfunction "PD0(INT0/OC0B)_6") (pintype "bidirectional"))
      (node (ref "U1") (pin "P97") (pinfunction "IO_L23P_2_P97") (pintype "bidirectional"))
    )
    (net (code "50") (name "/PD1") (class "Default")
      (node (ref "IC3") (pin "7") (pinfunction "PD1(INT1/AIN0)_7") (pintype "bidirectional"))
      (node (ref "U1") (pin "P96") (pinfunction "IO_L24N_2_P96") (pintype "bidirectional"))
    )
    (net (code "51") (name "/PD2") (class "Default")
      (node (ref "IC3") (pin "8") (pinfunction "PD2(INT2/AIN1/RXD1)_8") (pintype "bidirectional"))
      (node (ref "U1") (pin "P95") (pinfunction "IO_L24P_2_P95") (pintype "bidirectional"))
    )
    (net (code "52") (name "/PD3") (class "Default")
      (node (ref "IC3") (pin "9") (pinfunction "PD3(INT3/TXD1)_9") (pintype "bidirectional"))
      (node (ref "U1") (pin "P93") (pinfunction "IO_L40N_2_P93") (pintype "bidirectional"))
    )
    (net (code "53") (name "/PD4") (class "Default")
      (node (ref "IC3") (pin "10") (pinfunction "PD4(INT5/AIN3)_10") (pintype "bidirectional"))
      (node (ref "U1") (pin "P92") (pinfunction "IO_L40P_2VREF_2_P92") (pintype "bidirectional"))
    )
    (net (code "54") (name "/PD5") (class "Default")
      (node (ref "IC3") (pin "11") (pinfunction "PD5(XCK/AIN4/PCINT12)_11") (pintype "bidirectional"))
      (node (ref "U1") (pin "P90") (pinfunction "IO_L40N_3VREF_3_P90") (pintype "bidirectional"))
    )
    (net (code "55") (name "/PD6") (class "Default")
      (node (ref "IC3") (pin "12") (pinfunction "PD6(INT6/AIN5/RTS)_12") (pintype "bidirectional"))
      (node (ref "U1") (pin "P89") (pinfunction "IO_L40P_3_P89") (pintype "bidirectional"))
    )
    (net (code "56") (name "/PROM_DO") (class "Default")
      (node (ref "IC1") (pin "1") (pinfunction "DO_1") (pintype "bidirectional"))
      (node (ref "U1") (pin "P65") (pinfunction "IO_L27N_4DIND0_P65") (pintype "bidirectional"))
    )
    (net (code "57") (name "/PROM_INITB") (class "Default")
      (node (ref "IC1") (pin "8") (pinfunction "OE/RESET_8") (pintype "bidirectional"))
      (node (ref "U1") (pin "P58") (pinfunction "IO_L31N_4INIT_B_P58") (pintype "bidirectional"))
    )
    (net (code "58") (name "/PS2CLK") (class "Default")
      (node (ref "R4") (pin "1") (pinfunction "1_1") (pintype "passive"))
      (node (ref "R47") (pin "2") (pinfunction "2_2") (pintype "passive"))
      (node (ref "T1") (pin "2") (pinfunction "S_2") (pintype "passive"))
      (node (ref "U1") (pin "P46") (pinfunction "IO_L28P_5D7_P46") (pintype "bidirectional"))
    )
    (net (code "59") (name "/PS2DAT") (class "Default")
      (node (ref "R51") (pin "2") (pinfunction "2_2") (pintype "passive"))
      (node (ref "R6") (pin "1") (pinfunction "1_1") (pintype "passive"))
      (node (ref "T3") (pin "2") (pinfunction "S_2") (pintype "passive"))
      (node (ref "U1") (pin "P44") (pinfunction "IOVREF_5_P44") (pintype "bidirectional"))
    )
    (net (code "60") (name "/R0") (class "Default")
      (node (ref "R10") (pin "1") (pinfunction "1_1") (pintype "passive"))
      (node (ref "U1") (pin "P55") (pinfunction "IO_L32P_4GCLK0_P55") (pintype "bidirectional"))
    )
    (net (code "61") (name "/R1") (class "Default")
      (node (ref "R9") (pin "1") (pinfunction "1_1") (pintype "passive"))
      (node (ref "U1") (pin "P53") (pinfunction "IO_L32N_5GCLK3_P53") (pintype "bidirectional"))
    )
    (net (code "62") (name "/SCART_BLANKING") (class "Default")
      (node (ref "R50") (pin "1") (pinfunction "1_1") (pintype "passive"))
      (node (ref "X1") (pin "16") (pinfunction "16_16") (pintype "passive"))
    )
    (net (code "63") (name "/SCART_BLUE") (class "Default")
      (node (ref "R31") (pin "1") (pinfunction "1_1") (pintype "passive"))
      (node (ref "R32") (pin "1") (pinfunction "1_1") (pintype "passive"))
      (node (ref "R33") (pin "1") (pinfunction "1_1") (pintype "passive"))
      (node (ref "X1") (pin "7") (pinfunction "7_7") (pintype "passive"))
    )
    (net (code "64") (name "/SCART_COMP") (class "Default")
      (node (ref "R13") (pin "1") (pinfunction "1_1") (pintype "passive"))
      (node (ref "R14") (pin "1") (pinfunction "1_1") (pintype "passive"))
      (node (ref "X1") (pin "19") (pinfunction "19_19") (pintype "passive"))
    )
    (net (code "65") (name "/SCART_GREEN") (class "Default")
      (node (ref "R26") (pin "1") (pinfunction "1_1") (pintype "passive"))
      (node (ref "R27") (pin "1") (pinfunction "1_1") (pintype "passive"))
      (node (ref "R28") (pin "1") (pinfunction "1_1") (pintype "passive"))
      (node (ref "X1") (pin "11") (pinfunction "11_11") (pintype "passive"))
    )
    (net (code "66") (name "/SCART_LEFT") (class "Default")
      (node (ref "C3") (pin "2") (pinfunction "2_2") (pintype "passive"))
      (node (ref "X1") (pin "3") (pinfunction "3_3") (pintype "passive"))
    )
    (net (code "67") (name "/SCART_MODE") (class "Default")
      (node (ref "X1") (pin "8") (pinfunction "8_8") (pintype "passive"))
    )
    (net (code "68") (name "/SCART_RED") (class "Default")
      (node (ref "R15") (pin "1") (pinfunction "1_1") (pintype "passive"))
      (node (ref "R16") (pin "1") (pinfunction "1_1") (pintype "passive"))
      (node (ref "R20") (pin "1") (pinfunction "1_1") (pintype "passive"))
      (node (ref "X1") (pin "15") (pinfunction "15_15") (pintype "passive"))
    )
    (net (code "69") (name "/SCART_RIGHT") (class "Default")
      (node (ref "C4") (pin "2") (pinfunction "2_2") (pintype "passive"))
      (node (ref "X1") (pin "1") (pinfunction "1_1") (pintype "passive"))
    )
    (net (code "70") (name "/SD_CLK") (class "Default")
      (node (ref "U$3") (pin "5") (pinfunction "SCLK_5") (pintype "input"))
      (node (ref "U1") (pin "P41") (pinfunction "IO_L01N_5RDWR_B_P41") (pintype "bidirectional"))
    )
    (net (code "71") (name "/SD_CS") (class "Default")
      (node (ref "U$3") (pin "1") (pinfunction "CS_1") (pintype "input"))
      (node (ref "U1") (pin "P141") (pinfunction "IO_L01N_0VRP_0_P141") (pintype "bidirectional"))
    )
    (net (code "72") (name "/SD_DI") (class "Default")
      (node (ref "U$3") (pin "2") (pinfunction "DATA_IN_2") (pintype "input"))
      (node (ref "U1") (pin "P140") (pinfunction "IO_L01P_0VRN_0_P140") (pintype "bidirectional"))
    )
    (net (code "73") (name "/SD_DO") (class "Default")
      (node (ref "U$3") (pin "7") (pinfunction "DATA_OUT_7") (pintype "output"))
      (node (ref "U1") (pin "P40") (pinfunction "IO_L01P_5CS_B_P40") (pintype "bidirectional"))
    )
    (net (code "74") (name "/SPI_MISO") (class "Default")
      (node (ref "IC3") (pin "17") (pinfunction "PB3(PDO/MISO/PCINT3)_17") (pintype "bidirectional"))
      (node (ref "SV4") (pin "14") (pinfunction "14_14") (pintype "passive"))
    )
    (net (code "75") (name "/SPI_MOSI") (class "Default")
      (node (ref "IC3") (pin "16") (pinfunction "PB2(PDI/MOSI/PCINT2)_16") (pintype "bidirectional"))
      (node (ref "SV4") (pin "18") (pinfunction "18_18") (pintype "passive"))
    )
    (net (code "76") (name "/SPI_SCLK") (class "Default")
      (node (ref "IC3") (pin "15") (pinfunction "PB1(SCK/PCINT1)_15") (pintype "bidirectional"))
      (node (ref "SV4") (pin "16") (pinfunction "16_16") (pintype "passive"))
    )
    (net (code "77") (name "/SPI_SEL") (class "Default")
      (node (ref "IC3") (pin "14") (pinfunction "PB0(SS/PCINT0)_14") (pintype "bidirectional"))
      (node (ref "SV4") (pin "12") (pinfunction "12_12") (pintype "passive"))
    )
    (net (code "78") (name "/TCK") (class "Default")
      (node (ref "IC1") (pin "6") (pinfunction "TCK_6") (pintype "bidirectional"))
      (node (ref "IC3") (pin "19") (pinfunction "PB5(PCINT5)_19") (pintype "bidirectional"))
      (node (ref "R2") (pin "2") (pinfunction "2_2") (pintype "passive"))
      (node (ref "SV4") (pin "7") (pinfunction "7_7") (pintype "passive"))
    )
    (net (code "79") (name "/TDI_FPGA") (class "Default")
      (node (ref "IC3") (pin "21") (pinfunction "PB7(OC0A/OC1C/PCINT7)_21") (pintype "bidirectional"))
      (node (ref "R1") (pin "2") (pinfunction "2_2") (pintype "passive"))
      (node (ref "SV4") (pin "5") (pinfunction "5_5") (pintype "passive"))
    )
    (net (code "80") (name "/TDO_EXP") (class "Default")
      (node (ref "IC3") (pin "23") (pinfunction "PC6(OC1A/PCINT8)_23") (pintype "bidirectional"))
      (node (ref "SV4") (pin "6") (pinfunction "6_6") (pintype "passive"))
    )
    (net (code "81") (name "/TDO_PROM") (class "Default")
      (node (ref "IC1") (pin "17") (pinfunction "TDO_17") (pintype "bidirectional"))
      (node (ref "IC3") (pin "20") (pinfunction "PB6(PCINT6)_20") (pintype "bidirectional"))
      (node (ref "SV4") (pin "8") (pinfunction "8_8") (pintype "passive"))
    )
    (net (code "82") (name "/TMS") (class "Default")
      (node (ref "IC1") (pin "5") (pinfunction "TMS_5") (pintype "bidirectional"))
      (node (ref "IC3") (pin "18") (pinfunction "PB4(T1/PCINT4)_18") (pintype "bidirectional"))
      (node (ref "R3") (pin "2") (pinfunction "2_2") (pintype "passive"))
      (node (ref "SV4") (pin "10") (pinfunction "10_10") (pintype "passive"))
    )
    (net (code "83") (name "/VCC") (class "Default")
      (node (ref "C10") (pin "1") (pinfunction "1_1") (pintype "passive"))
      (node (ref "C11") (pin "1") (pinfunction "1_1") (pintype "passive"))
      (node (ref "C12") (pin "1") (pinfunction "1_1") (pintype "passive"))
      (node (ref "C13") (pin "1") (pinfunction "1_1") (pintype "passive"))
      (node (ref "C14") (pin "1") (pinfunction "1_1") (pintype "passive"))
      (node (ref "C15") (pin "1") (pinfunction "1_1") (pintype "passive"))
      (node (ref "C16") (pin "1") (pinfunction "1_1") (pintype "passive"))
      (node (ref "C17") (pin "1") (pinfunction "1_1") (pintype "passive"))
      (node (ref "C26") (pin "1") (pinfunction "1_1") (pintype "passive"))
      (node (ref "C27") (pin "1") (pinfunction "1_1") (pintype "passive"))
      (node (ref "C28") (pin "1") (pinfunction "1_1") (pintype "passive"))
      (node (ref "C29") (pin "1") (pinfunction "1_1") (pintype "passive"))
      (node (ref "C30") (pin "1") (pinfunction "1_1") (pintype "passive"))
      (node (ref "C31") (pin "1") (pinfunction "1_1") (pintype "passive"))
      (node (ref "C32") (pin "1") (pinfunction "1_1") (pintype "passive"))
      (node (ref "C34") (pin "1") (pinfunction "1_1") (pintype "passive"))
      (node (ref "C39") (pin "+") (pinfunction "+_+") (pintype "passive"))
      (node (ref "C6") (pin "1") (pinfunction "1_1") (pintype "passive"))
      (node (ref "C7") (pin "1") (pinfunction "1_1") (pintype "passive"))
      (node (ref "C8") (pin "1") (pinfunction "1_1") (pintype "passive"))
      (node (ref "C9") (pin "1") (pinfunction "1_1") (pintype "passive"))
      (node (ref "IC1") (pin "18") (pinfunction "VCCINT_18") (pintype "bidirectional"))
      (node (ref "IC1") (pin "19") (pinfunction "VCCO_19") (pintype "bidirectional"))
      (node (ref "IC1") (pin "20") (pinfunction "VCCJ_20") (pintype "bidirectional"))
      (node (ref "IC2") (pin "8") (pinfunction "VCC_8") (pintype "power_in"))
      (node (ref "IC3") (pin "31") (pinfunction "UVCC_31") (pintype "bidirectional"))
      (node (ref "IC3") (pin "32") (pinfunction "AVCC_32") (pintype "bidirectional"))
      (node (ref "IC3") (pin "4") (pinfunction "VCC_4") (pintype "bidirectional"))
      (node (ref "Q5") (pin "3") (pinfunction "C_3") (pintype "passive"))
      (node (ref "Q6") (pin "3") (pinfunction "C_3") (pintype "passive"))
      (node (ref "Q7") (pin "3") (pinfunction "C_3") (pintype "passive"))
      (node (ref "Q8") (pin "3") (pinfunction "C_3") (pintype "passive"))
      (node (ref "R22") (pin "1") (pinfunction "1_1") (pintype "passive"))
      (node (ref "R35") (pin "2") (pinfunction "2_2") (pintype "passive"))
      (node (ref "R36") (pin "2") (pinfunction "2_2") (pintype "passive"))
      (node (ref "R37") (pin "2") (pinfunction "2_2") (pintype "passive"))
      (node (ref "R38") (pin "2") (pinfunction "2_2") (pintype "passive"))
      (node (ref "R39") (pin "2") (pinfunction "2_2") (pintype "passive"))
      (node (ref "R4") (pin "2") (pinfunction "2_2") (pintype "passive"))
      (node (ref "R40") (pin "1") (pinfunction "1_1") (pintype "passive"))
      (node (ref "R41") (pin "1") (pinfunction "1_1") (pintype "passive"))
      (node (ref "R42") (pin "1") (pinfunction "1_1") (pintype "passive"))
      (node (ref "R43") (pin "1") (pinfunction "1_1") (pintype "passive"))
      (node (ref "R44") (pin "1") (pinfunction "1_1") (pintype "passive"))
      (node (ref "R45") (pin "1") (pinfunction "1_1") (pintype "passive"))
      (node (ref "R46") (pin "2") (pinfunction "2_2") (pintype "passive"))
      (node (ref "R55") (pin "1") (pinfunction "1_1") (pintype "passive"))
      (node (ref "R56") (pin "1") (pinfunction "1_1") (pintype "passive"))
      (node (ref "R6") (pin "2") (pinfunction "2_2") (pintype "passive"))
      (node (ref "SV2") (pin "4") (pinfunction "4_4") (pintype "passive"))
      (node (ref "SV2") (pin "6") (pinfunction "6_6") (pintype "passive"))
      (node (ref "SV3") (pin "1") (pinfunction "1_1") (pintype "passive"))
      (node (ref "SV4") (pin "19") (pinfunction "19_19") (pintype "passive"))
      (node (ref "SV4") (pin "20") (pinfunction "20_20") (pintype "passive"))
      (node (ref "SV5") (pin "3") (pinfunction "3_3") (pintype "passive"))
      (node (ref "SV5") (pin "4") (pinfunction "4_4") (pintype "passive"))
      (node (ref "T1") (pin "3") (pinfunction "G_3") (pintype "passive"))
      (node (ref "T2") (pin "3") (pinfunction "C_3") (pintype "passive"))
      (node (ref "T3") (pin "3") (pinfunction "G_3") (pintype "passive"))
      (node (ref "U$2") (pin "VDD") (pinfunction "VDD_VDD") (pintype "power_in"))
      (node (ref "U$3") (pin "4") (pinfunction "VDD_4") (pintype "power_in"))
      (node (ref "U$4") (pin "4") (pinfunction "VOUT1_4") (pintype "bidirectional"))
      (node (ref "U$6") (pin "P8") (pinfunction "VCC_P8") (pintype "bidirectional"))
      (node (ref "U1") (pin "P106") (pinfunction "VCCO_RIGHT2_P106") (pintype "passive"))
      (node (ref "U1") (pin "P115") (pinfunction "VCCO_TOP0_P115") (pintype "passive"))
      (node (ref "U1") (pin "P126") (pinfunction "VCCO_TOP1_P126") (pintype "passive"))
      (node (ref "U1") (pin "P138") (pinfunction "VCCO_TOP2_P138") (pintype "passive"))
      (node (ref "U1") (pin "P19") (pinfunction "VCCO_LEFT1_P19") (pintype "passive"))
      (node (ref "U1") (pin "P3") (pinfunction "VCCO_LEFT0_P3") (pintype "passive"))
      (node (ref "U1") (pin "P34") (pinfunction "VCCO_LEFT2_P34") (pintype "passive"))
      (node (ref "U1") (pin "P43") (pinfunction "VCCO_BOTTOM0_P43") (pintype "passive"))
      (node (ref "U1") (pin "P54") (pinfunction "VCCO_BOTTOM1_P54") (pintype "passive"))
      (node (ref "U1") (pin "P66") (pinfunction "VCCO_BOTTOM2_P66") (pintype "passive"))
      (node (ref "U1") (pin "P75") (pinfunction "VCCO_RIGHT0_P75") (pintype "passive"))
      (node (ref "U1") (pin "P91") (pinfunction "VCCO_RIGHT1_P91") (pintype "passive"))
    )
    (net (code "84") (name "/VCC5") (class "Default")
      (node (ref "C33") (pin "+") (pinfunction "+_+") (pintype "passive"))
      (node (ref "PWR_HDR") (pin "2") (pinfunction "2_2") (pintype "passive"))
      (node (ref "R5") (pin "2") (pinfunction "2_2") (pintype "passive"))
      (node (ref "R7") (pin "2") (pinfunction "2_2") (pintype "passive"))
      (node (ref "REG1.2") (pin "3") (pinfunction "VCC_3") (pintype "bidirectional"))
      (node (ref "REG2.5") (pin "3") (pinfunction "VCC_3") (pintype "bidirectional"))
      (node (ref "SV5") (pin "10") (pinfunction "10_10") (pintype "passive"))
      (node (ref "SV5") (pin "9") (pinfunction "9_9") (pintype "passive"))
      (node (ref "U$4") (pin "3") (pinfunction "VCC_3") (pintype "bidirectional"))
      (node (ref "X3") (pin "5") (pinfunction "5_5") (pintype "passive"))
      (node (ref "X7") (pin "2") (pinfunction "2_2") (pintype "power_in"))
    )
    (net (code "85") (name "/VCCAUX") (class "Default")
      (node (ref "C18") (pin "1") (pinfunction "1_1") (pintype "passive"))
      (node (ref "C19") (pin "1") (pinfunction "1_1") (pintype "passive"))
      (node (ref "C20") (pin "1") (pinfunction "1_1") (pintype "passive"))
      (node (ref "C21") (pin "1") (pinfunction "1_1") (pintype "passive"))
      (node (ref "C40") (pin "+") (pinfunction "+_+") (pintype "passive"))
      (node (ref "R50") (pin "2") (pinfunction "2_2") (pintype "passive"))
      (node (ref "REG2.5") (pin "4") (pinfunction "VOUT1_4") (pintype "bidirectional"))
      (node (ref "SV5") (pin "2") (pinfunction "2_2") (pintype "passive"))
      (node (ref "U1") (pin "P120") (pinfunction "VCCAUX2_P120") (pintype "passive"))
      (node (ref "U1") (pin "P134") (pinfunction "VCCAUX3_P134") (pintype "passive"))
      (node (ref "U1") (pin "P48") (pinfunction "VCCAUX0_P48") (pintype "passive"))
      (node (ref "U1") (pin "P62") (pinfunction "VCCAUX1_P62") (pintype "passive"))
    )
    (net (code "86") (name "/VCCINT") (class "Default")
      (node (ref "C22") (pin "1") (pinfunction "1_1") (pintype "passive"))
      (node (ref "C23") (pin "1") (pinfunction "1_1") (pintype "passive"))
      (node (ref "C24") (pin "1") (pinfunction "1_1") (pintype "passive"))
      (node (ref "C25") (pin "1") (pinfunction "1_1") (pintype "passive"))
      (node (ref "C42") (pin "+") (pinfunction "+_+") (pintype "passive"))
      (node (ref "REG1.2") (pin "4") (pinfunction "VOUT1_4") (pintype "bidirectional"))
      (node (ref "SV5") (pin "1") (pinfunction "1_1") (pintype "passive"))
      (node (ref "U1") (pin "P121") (pinfunction "VCCINT2_P121") (pintype "passive"))
      (node (ref "U1") (pin "P133") (pinfunction "VCCINT3_P133") (pintype "passive"))
      (node (ref "U1") (pin "P49") (pinfunction "VCCINT0_P49") (pintype "passive"))
      (node (ref "U1") (pin "P61") (pinfunction "VCCINT1_P61") (pintype "passive"))
    )
    (net (code "87") (name "/X3") (class "Default")
      (node (ref "SV2") (pin "5") (pinfunction "5_5") (pintype "passive"))
      (node (ref "U1") (pin "P76") (pinfunction "IO_P76") (pintype "bidirectional"))
    )
    (net (code "88") (name "/X4") (class "Default")
      (node (ref "SV2") (pin "3") (pinfunction "3_3") (pintype "passive"))
      (node (ref "U1") (pin "P77") (pinfunction "IO_L20P_3_P77") (pintype "bidirectional"))
    )
    (net (code "89") (name "/X8") (class "Default")
      (node (ref "SV2") (pin "1") (pinfunction "1_1") (pintype "passive"))
      (node (ref "U1") (pin "P74") (pinfunction "IO_L01N_3VRP_3_P74") (pintype "bidirectional"))
    )
    (net (code "91") (name "GND") (class "Default")
      (node (ref "C1") (pin "1") (pinfunction "1_1") (pintype "passive"))
      (node (ref "C10") (pin "2") (pinfunction "2_2") (pintype "passive"))
      (node (ref "C11") (pin "2") (pinfunction "2_2") (pintype "passive"))
      (node (ref "C12") (pin "2") (pinfunction "2_2") (pintype "passive"))
      (node (ref "C13") (pin "2") (pinfunction "2_2") (pintype "passive"))
      (node (ref "C14") (pin "2") (pinfunction "2_2") (pintype "passive"))
      (node (ref "C15") (pin "2") (pinfunction "2_2") (pintype "passive"))
      (node (ref "C16") (pin "2") (pinfunction "2_2") (pintype "passive"))
      (node (ref "C17") (pin "2") (pinfunction "2_2") (pintype "passive"))
      (node (ref "C18") (pin "2") (pinfunction "2_2") (pintype "passive"))
      (node (ref "C19") (pin "2") (pinfunction "2_2") (pintype "passive"))
      (node (ref "C20") (pin "2") (pinfunction "2_2") (pintype "passive"))
      (node (ref "C21") (pin "2") (pinfunction "2_2") (pintype "passive"))
      (node (ref "C22") (pin "2") (pinfunction "2_2") (pintype "passive"))
      (node (ref "C23") (pin "2") (pinfunction "2_2") (pintype "passive"))
      (node (ref "C24") (pin "2") (pinfunction "2_2") (pintype "passive"))
      (node (ref "C25") (pin "2") (pinfunction "2_2") (pintype "passive"))
      (node (ref "C26") (pin "2") (pinfunction "2_2") (pintype "passive"))
      (node (ref "C27") (pin "2") (pinfunction "2_2") (pintype "passive"))
      (node (ref "C28") (pin "2") (pinfunction "2_2") (pintype "passive"))
      (node (ref "C29") (pin "2") (pinfunction "2_2") (pintype "passive"))
      (node (ref "C30") (pin "2") (pinfunction "2_2") (pintype "passive"))
      (node (ref "C31") (pin "2") (pinfunction "2_2") (pintype "passive"))
      (node (ref "C32") (pin "2") (pinfunction "2_2") (pintype "passive"))
      (node (ref "C33") (pin "-") (pinfunction "-_-") (pintype "passive"))
      (node (ref "C34") (pin "2") (pinfunction "2_2") (pintype "passive"))
      (node (ref "C37") (pin "1") (pinfunction "1_1") (pintype "passive"))
      (node (ref "C38") (pin "1") (pinfunction "1_1") (pintype "passive"))
      (node (ref "C39") (pin "-") (pinfunction "-_-") (pintype "passive"))
      (node (ref "C40") (pin "-") (pinfunction "-_-") (pintype "passive"))
      (node (ref "C41") (pin "2") (pinfunction "2_2") (pintype "passive"))
      (node (ref "C42") (pin "-") (pinfunction "-_-") (pintype "passive"))
      (node (ref "C5") (pin "1") (pinfunction "1_1") (pintype "passive"))
      (node (ref "C6") (pin "2") (pinfunction "2_2") (pintype "passive"))
      (node (ref "C7") (pin "2") (pinfunction "2_2") (pintype "passive"))
      (node (ref "C8") (pin "2") (pinfunction "2_2") (pintype "passive"))
      (node (ref "C9") (pin "2") (pinfunction "2_2") (pintype "passive"))
      (node (ref "IC1") (pin "11") (pinfunction "GND_11") (pintype "bidirectional"))
      (node (ref "IC2") (pin "4") (pinfunction "GND_4") (pintype "power_in"))
      (node (ref "IC3") (pin "3") (pinfunction "GND_3") (pintype "bidirectional"))
      (node (ref "PWR_HDR") (pin "1") (pinfunction "1_1") (pintype "passive"))
      (node (ref "R17") (pin "1") (pinfunction "1_1") (pintype "passive"))
      (node (ref "R19") (pin "1") (pinfunction "1_1") (pintype "passive"))
      (node (ref "R21") (pin "1") (pinfunction "1_1") (pintype "passive"))
      (node (ref "REG1.2") (pin "1") (pinfunction "GND_1") (pintype "bidirectional"))
      (node (ref "REG2.5") (pin "1") (pinfunction "GND_1") (pintype "bidirectional"))
      (node (ref "SV2") (pin "2") (pinfunction "2_2") (pintype "passive"))
      (node (ref "SV3") (pin "2") (pinfunction "2_2") (pintype "passive"))
      (node (ref "SV4") (pin "3") (pinfunction "3_3") (pintype "passive"))
      (node (ref "SV4") (pin "4") (pinfunction "4_4") (pintype "passive"))
      (node (ref "SV5") (pin "7") (pinfunction "7_7") (pintype "passive"))
      (node (ref "U$1") (pin "GND") (pinfunction "GND_GND") (pintype "bidirectional"))
      (node (ref "U$2") (pin "GND") (pinfunction "GND_GND") (pintype "power_in"))
      (node (ref "U$3") (pin "3") (pinfunction "VSS1_3") (pintype "power_in"))
      (node (ref "U$3") (pin "6") (pinfunction "VSS2_6") (pintype "power_in"))
      (node (ref "U$3") (pin "MT1") (pinfunction "COMMON_SW_MT1") (pintype "passive"))
      (node (ref "U$3") (pin "MT3") (pinfunction "GND_MT3") (pintype "power_in"))
      (node (ref "U$4") (pin "1") (pinfunction "GND_1") (pintype "bidirectional"))
      (node (ref "U$6") (pin "P24") (pinfunction "VSS_P24") (pintype "bidirectional"))
      (node (ref "U$6") (pin "P30") (pinfunction "CE_P30") (pintype "bidirectional"))
      (node (ref "U$7") (pin "GND") (pinfunction "GND_GND") (pintype "bidirectional"))
      (node (ref "U$8") (pin "GND") (pinfunction "GND_GND") (pintype "bidirectional"))
      (node (ref "U$9") (pin "GND") (pinfunction "GND_GND") (pintype "bidirectional"))
      (node (ref "U1") (pin "P101") (pinfunction "GND11_P101") (pintype "passive"))
      (node (ref "U1") (pin "P114") (pinfunction "GND12_P114") (pintype "passive"))
      (node (ref "U1") (pin "P117") (pinfunction "GND13_P117") (pintype "passive"))
      (node (ref "U1") (pin "P136") (pinfunction "GND14_P136") (pintype "passive"))
      (node (ref "U1") (pin "P139") (pinfunction "GND15_P139") (pintype "passive"))
      (node (ref "U1") (pin "P16") (pinfunction "GND1_P16") (pintype "passive"))
      (node (ref "U1") (pin "P22") (pinfunction "GND2_P22") (pintype "passive"))
      (node (ref "U1") (pin "P29") (pinfunction "GND3_P29") (pintype "passive"))
      (node (ref "U1") (pin "P37") (pinfunction "M1_P37") (pintype "bidirectional"))
      (node (ref "U1") (pin "P38") (pinfunction "M0_P38") (pintype "bidirectional"))
      (node (ref "U1") (pin "P39") (pinfunction "M2_P39") (pintype "bidirectional"))
      (node (ref "U1") (pin "P42") (pinfunction "GND4_P42") (pintype "passive"))
      (node (ref "U1") (pin "P45") (pinfunction "GND5_P45") (pintype "passive"))
      (node (ref "U1") (pin "P64") (pinfunction "GND6_P64") (pintype "passive"))
      (node (ref "U1") (pin "P67") (pinfunction "GND7_P67") (pintype "passive"))
      (node (ref "U1") (pin "P81") (pinfunction "GND8_P81") (pintype "passive"))
      (node (ref "U1") (pin "P88") (pinfunction "GND9_P88") (pintype "passive"))
      (node (ref "U1") (pin "P9") (pinfunction "GND0_P9") (pintype "passive"))
      (node (ref "U1") (pin "P94") (pinfunction "GND10_P94") (pintype "passive"))
      (node (ref "X1") (pin "13") (pinfunction "13_13") (pintype "passive"))
      (node (ref "X1") (pin "14") (pinfunction "14_14") (pintype "passive"))
      (node (ref "X1") (pin "17") (pinfunction "17_17") (pintype "passive"))
      (node (ref "X1") (pin "18") (pinfunction "18_18") (pintype "passive"))
      (node (ref "X1") (pin "21") (pinfunction "21_21") (pintype "passive"))
      (node (ref "X1") (pin "4") (pinfunction "4_4") (pintype "passive"))
      (node (ref "X1") (pin "5") (pinfunction "5_5") (pintype "passive"))
      (node (ref "X1") (pin "9") (pinfunction "9_9") (pintype "passive"))
      (node (ref "X3") (pin "3") (pinfunction "3_3") (pintype "passive"))
      (node (ref "X3") (pin "SH1") (pinfunction "PE1_SH1") (pintype "power_in"))
      (node (ref "X3") (pin "SH2") (pinfunction "PE2_SH2") (pintype "power_in"))
      (node (ref "X3") (pin "SH3") (pinfunction "PE3_SH3") (pintype "power_in"))
      (node (ref "X4") (pin "8") (pinfunction "F_8") (pintype "passive"))
      (node (ref "X4") (pin "G1") (pinfunction "G1_G1") (pintype "passive"))
      (node (ref "X5") (pin "8") (pinfunction "F_8") (pintype "passive"))
      (node (ref "X5") (pin "G1") (pinfunction "G1_G1") (pintype "passive"))
      (node (ref "X7") (pin "3") (pinfunction "3_3") (pintype "power_in"))
      (node (ref "X8") (pin "1") (pinfunction "1_1") (pintype "passive"))
    )
    (net (code "92") (name "Net-(C1-Pad2)") (class "Default")
      (node (ref "C1") (pin "2") (pinfunction "2_2") (pintype "passive"))
      (node (ref "R23") (pin "2") (pinfunction "2_2") (pintype "passive"))
      (node (ref "R48") (pin "1") (pinfunction "1_1") (pintype "passive"))
    )
    (net (code "93") (name "Net-(C2-Pad1)") (class "Default")
      (node (ref "C2") (pin "1") (pinfunction "1_1") (pintype "passive"))
      (node (ref "R17") (pin "2") (pinfunction "2_2") (pintype "passive"))
      (node (ref "X8") (pin "2") (pinfunction "2_2") (pintype "passive"))
      (node (ref "X8") (pin "3") (pinfunction "3_3") (pintype "passive"))
      (node (ref "X8") (pin "4") (pinfunction "4_4") (pintype "passive"))
      (node (ref "X8") (pin "5") (pinfunction "5_5") (pintype "passive"))
    )
    (net (code "94") (name "Net-(C3-Pad1)") (class "Default")
      (node (ref "C3") (pin "1") (pinfunction "1_1") (pintype "passive"))
      (node (ref "R48") (pin "2") (pinfunction "2_2") (pintype "passive"))
    )
    (net (code "95") (name "Net-(C4-Pad1)") (class "Default")
      (node (ref "C4") (pin "1") (pinfunction "1_1") (pintype "passive"))
      (node (ref "R49") (pin "2") (pinfunction "2_2") (pintype "passive"))
    )
    (net (code "96") (name "Net-(C5-Pad2)") (class "Default")
      (node (ref "C5") (pin "2") (pinfunction "2_2") (pintype "passive"))
      (node (ref "R34") (pin "2") (pinfunction "2_2") (pintype "passive"))
      (node (ref "R49") (pin "1") (pinfunction "1_1") (pintype "passive"))
    )
    (net (code "97") (name "Net-(C38-Pad2)") (class "Default")
      (node (ref "C38") (pin "2") (pinfunction "2_2") (pintype "passive"))
      (node (ref "JP2") (pin "1") (pinfunction "1_1") (pintype "passive"))
      (node (ref "Q1") (pin "2") (pinfunction "2_2") (pintype "passive"))
    )
    (net (code "98") (name "Net-(IC1-CLK)") (class "Default")
      (node (ref "IC1") (pin "3") (pinfunction "CLK_3") (pintype "bidirectional"))
      (node (ref "U1") (pin "P72") (pinfunction "CCLK_P72") (pintype "bidirectional"))
    )
    (net (code "99") (name "Net-(IC1-TDI)") (class "Default")
      (node (ref "IC1") (pin "4") (pinfunction "TDI_4") (pintype "bidirectional"))
      (node (ref "U1") (pin "P109") (pinfunction "TDO_P109") (pintype "bidirectional"))
    )
    (net (code "100") (name "Net-(IC1-{slash}CE)") (class "Default")
      (node (ref "IC1") (pin "10") (pinfunction "/CE_10") (pintype "bidirectional"))
      (node (ref "U1") (pin "P71") (pinfunction "DONE_P71") (pintype "bidirectional"))
    )
    (net (code "101") (name "Net-(IC1-{slash}CF)") (class "Default")
      (node (ref "IC1") (pin "7") (pinfunction "/CF_7") (pintype "bidirectional"))
      (node (ref "U1") (pin "P143") (pinfunction "PROG_B_P143") (pintype "bidirectional"))
    )
    (net (code "102") (name "Net-(IC3-D+)") (class "Default")
      (node (ref "IC3") (pin "29") (pinfunction "D+_29") (pintype "bidirectional"))
      (node (ref "R54") (pin "2") (pinfunction "2_2") (pintype "passive"))
    )
    (net (code "103") (name "Net-(IC3-D-)") (class "Default")
      (node (ref "IC3") (pin "30") (pinfunction "D-_30") (pintype "bidirectional"))
      (node (ref "R53") (pin "2") (pinfunction "2_2") (pintype "passive"))
    )
    (net (code "104") (name "Net-(IC3-UCAP)") (class "Default")
      (node (ref "C41") (pin "1") (pinfunction "1_1") (pintype "passive"))
      (node (ref "IC3") (pin "27") (pinfunction "UCAP_27") (pintype "bidirectional"))
    )
    (net (code "105") (name "Net-(IC3-UGND)") (class "Default")
      (node (ref "IC3") (pin "28") (pinfunction "UGND_28") (pintype "bidirectional"))
      (node (ref "X6") (pin "4") (pinfunction "4_4") (pintype "passive"))
    )
    (net (code "106") (name "Net-(IC3-XTAL1)") (class "Default")
      (node (ref "IC3") (pin "1") (pinfunction "XTAL1_1") (pintype "bidirectional"))
      (node (ref "JP2") (pin "2") (pinfunction "2_2") (pintype "passive"))
    )
    (net (code "107") (name "Net-(IC3-XTAL2{slash}PC0)") (class "Default")
      (node (ref "C37") (pin "2") (pinfunction "2_2") (pintype "passive"))
      (node (ref "IC3") (pin "2") (pinfunction "XTAL2/PC0_2") (pintype "bidirectional"))
      (node (ref "Q1") (pin "1") (pinfunction "1_1") (pintype "passive"))
    )
    (net (code "108") (name "Net-(Q5-B)") (class "Default")
      (node (ref "Q5") (pin "1") (pinfunction "B_1") (pintype "passive"))
      (node (ref "R8") (pin "2") (pinfunction "2_2") (pintype "passive"))
    )
    (net (code "109") (name "Net-(Q5-E)") (class "Default")
      (node (ref "Q5") (pin "2") (pinfunction "E_2") (pintype "passive"))
      (node (ref "R13") (pin "2") (pinfunction "2_2") (pintype "passive"))
      (node (ref "R14") (pin "2") (pinfunction "2_2") (pintype "passive"))
    )
    (net (code "110") (name "Net-(Q6-B)") (class "Default")
      (node (ref "Q6") (pin "1") (pinfunction "B_1") (pintype "passive"))
      (node (ref "R10") (pin "2") (pinfunction "2_2") (pintype "passive"))
      (node (ref "R9") (pin "2") (pinfunction "2_2") (pintype "passive"))
    )
    (net (code "111") (name "Net-(Q6-E)") (class "Default")
      (node (ref "Q6") (pin "2") (pinfunction "E_2") (pintype "passive"))
      (node (ref "R15") (pin "2") (pinfunction "2_2") (pintype "passive"))
      (node (ref "R16") (pin "2") (pinfunction "2_2") (pintype "passive"))
      (node (ref "R20") (pin "2") (pinfunction "2_2") (pintype "passive"))
    )
    (net (code "112") (name "Net-(Q7-B)") (class "Default")
      (node (ref "Q7") (pin "1") (pinfunction "B_1") (pintype "passive"))
      (node (ref "R29") (pin "2") (pinfunction "2_2") (pintype "passive"))
      (node (ref "R30") (pin "2") (pinfunction "2_2") (pintype "passive"))
    )
    (net (code "113") (name "Net-(Q7-E)") (class "Default")
      (node (ref "Q7") (pin "2") (pinfunction "E_2") (pintype "passive"))
      (node (ref "R31") (pin "2") (pinfunction "2_2") (pintype "passive"))
      (node (ref "R32") (pin "2") (pinfunction "2_2") (pintype "passive"))
      (node (ref "R33") (pin "2") (pinfunction "2_2") (pintype "passive"))
    )
    (net (code "114") (name "Net-(Q8-B)") (class "Default")
      (node (ref "Q8") (pin "1") (pinfunction "B_1") (pintype "passive"))
      (node (ref "R24") (pin "2") (pinfunction "2_2") (pintype "passive"))
      (node (ref "R25") (pin "2") (pinfunction "2_2") (pintype "passive"))
    )
    (net (code "115") (name "Net-(Q8-E)") (class "Default")
      (node (ref "Q8") (pin "2") (pinfunction "E_2") (pintype "passive"))
      (node (ref "R26") (pin "2") (pinfunction "2_2") (pintype "passive"))
      (node (ref "R27") (pin "2") (pinfunction "2_2") (pintype "passive"))
      (node (ref "R28") (pin "2") (pinfunction "2_2") (pintype "passive"))
    )
    (net (code "116") (name "Net-(R18-Pad2)") (class "Default")
      (node (ref "R18") (pin "2") (pinfunction "2_2") (pintype "passive"))
      (node (ref "R22") (pin "2") (pinfunction "2_2") (pintype "passive"))
    )
    (net (code "117") (name "Net-(R53-Pad1)") (class "Default")
      (node (ref "R53") (pin "1") (pinfunction "1_1") (pintype "passive"))
      (node (ref "X6") (pin "2") (pinfunction "2_2") (pintype "passive"))
    )
    (net (code "118") (name "Net-(R54-Pad1)") (class "Default")
      (node (ref "R54") (pin "1") (pinfunction "1_1") (pintype "passive"))
      (node (ref "X6") (pin "3") (pinfunction "3_3") (pintype "passive"))
    )
    (net (code "119") (name "Net-(T2-B)") (class "Default")
      (node (ref "C2") (pin "2") (pinfunction "2_2") (pintype "passive"))
      (node (ref "R18") (pin "1") (pinfunction "1_1") (pintype "passive"))
      (node (ref "R19") (pin "2") (pinfunction "2_2") (pintype "passive"))
      (node (ref "T2") (pin "1") (pinfunction "B_1") (pintype "passive"))
    )
    (net (code "120") (name "Net-(U$6-A0)") (class "Default")
      (node (ref "U$6") (pin "P20") (pinfunction "A0_P20") (pintype "bidirectional"))
      (node (ref "U1") (pin "P24") (pinfunction "IO_L24N_6VREF_6_P24") (pintype "bidirectional"))
    )
    (net (code "121") (name "Net-(U$6-A1)") (class "Default")
      (node (ref "U$6") (pin "P19") (pinfunction "A1_P19") (pintype "bidirectional"))
      (node (ref "U1") (pin "P23") (pinfunction "IO_L24P_6_P23") (pintype "bidirectional"))
    )
    (net (code "122") (name "Net-(U$6-A2)") (class "Default")
      (node (ref "U$6") (pin "P18") (pinfunction "A2_P18") (pintype "bidirectional"))
      (node (ref "U1") (pin "P21") (pinfunction "IO_L40N_6_P21") (pintype "bidirectional"))
    )
    (net (code "123") (name "Net-(U$6-A3)") (class "Default")
      (node (ref "U$6") (pin "P17") (pinfunction "A3_P17") (pintype "bidirectional"))
      (node (ref "U1") (pin "P20") (pinfunction "IO_L40P_6VREF_6_P20") (pintype "bidirectional"))
    )
    (net (code "124") (name "Net-(U$6-A4)") (class "Default")
      (node (ref "U$6") (pin "P16") (pinfunction "A4_P16") (pintype "bidirectional"))
      (node (ref "U1") (pin "P18") (pinfunction "IO_L40N_7VREF_7_P18") (pintype "bidirectional"))
    )
    (net (code "125") (name "Net-(U$6-A5)") (class "Default")
      (node (ref "U$6") (pin "P15") (pinfunction "A5_P15") (pintype "bidirectional"))
      (node (ref "U1") (pin "P17") (pinfunction "IO_L40P_7_P17") (pintype "bidirectional"))
    )
    (net (code "126") (name "Net-(U$6-A6)") (class "Default")
      (node (ref "U$6") (pin "P14") (pinfunction "A6_P14") (pintype "bidirectional"))
      (node (ref "U1") (pin "P15") (pinfunction "IO_L24N_7_P15") (pintype "bidirectional"))
    )
    (net (code "127") (name "Net-(U$6-A7)") (class "Default")
      (node (ref "U$6") (pin "P13") (pinfunction "A7_P13") (pintype "bidirectional"))
      (node (ref "U1") (pin "P14") (pinfunction "IO_L24P_7_P14") (pintype "bidirectional"))
    )
    (net (code "128") (name "Net-(U$6-A8)") (class "Default")
      (node (ref "U$6") (pin "P3") (pinfunction "A8_P3") (pintype "bidirectional"))
      (node (ref "U1") (pin "P4") (pinfunction "IOVREF_7_P4") (pintype "bidirectional"))
    )
    (net (code "129") (name "Net-(U$6-A9)") (class "Default")
      (node (ref "U$6") (pin "P2") (pinfunction "A9_P2") (pintype "bidirectional"))
      (node (ref "U1") (pin "P2") (pinfunction "IO_L01N_7VRP_7_P2") (pintype "bidirectional"))
    )
    (net (code "130") (name "Net-(U$6-A10)") (class "Default")
      (node (ref "U$6") (pin "P31") (pinfunction "A10_P31") (pintype "bidirectional"))
      (node (ref "U1") (pin "P35") (pinfunction "IO_L01P_6VRN_6_P35") (pintype "bidirectional"))
    )
    (net (code "131") (name "Net-(U$6-A11)") (class "Default")
      (node (ref "U$6") (pin "P1") (pinfunction "A11_P1") (pintype "bidirectional"))
      (node (ref "U1") (pin "P1") (pinfunction "IO_L01P_7VRN_7_P1") (pintype "bidirectional"))
    )
    (net (code "132") (name "Net-(U$6-A12)") (class "Default")
      (node (ref "U$6") (pin "P12") (pinfunction "A12_P12") (pintype "bidirectional"))
      (node (ref "U1") (pin "P13") (pinfunction "IO_L23N_7_P13") (pintype "bidirectional"))
    )
    (net (code "133") (name "Net-(U$6-A13)") (class "Default")
      (node (ref "U$6") (pin "P4") (pinfunction "A13_P4") (pintype "bidirectional"))
      (node (ref "U1") (pin "P5") (pinfunction "IO_L20P_7_P5") (pintype "bidirectional"))
    )
    (net (code "134") (name "Net-(U$6-A14)") (class "Default")
      (node (ref "U$6") (pin "P11") (pinfunction "A14_P11") (pintype "bidirectional"))
      (node (ref "U1") (pin "P12") (pinfunction "IO_L23P_7_P12") (pintype "bidirectional"))
    )
    (net (code "135") (name "Net-(U$6-A15)") (class "Default")
      (node (ref "U$6") (pin "P7") (pinfunction "A15_P7") (pintype "bidirectional"))
      (node (ref "U1") (pin "P8") (pinfunction "IO_L21N_7_P8") (pintype "bidirectional"))
    )
    (net (code "136") (name "Net-(U$6-A16)") (class "Default")
      (node (ref "U$6") (pin "P10") (pinfunction "A16_P10") (pintype "bidirectional"))
      (node (ref "U1") (pin "P11") (pinfunction "IO_L22N_7_P11") (pintype "bidirectional"))
    )
    (net (code "137") (name "Net-(U$6-A17)") (class "Default")
      (node (ref "U$6") (pin "P6") (pinfunction "A17_P6") (pintype "bidirectional"))
      (node (ref "U1") (pin "P7") (pinfunction "IO_L21P_7_P7") (pintype "bidirectional"))
    )
    (net (code "138") (name "Net-(U$6-A18)") (class "Default")
      (node (ref "U$6") (pin "P9") (pinfunction "A18_P9") (pintype "bidirectional"))
      (node (ref "U1") (pin "P10") (pinfunction "IO_L22P_7_P10") (pintype "bidirectional"))
    )
    (net (code "139") (name "Net-(U$6-DQ0)") (class "Default")
      (node (ref "U$6") (pin "P21") (pinfunction "DQ0_P21") (pintype "bidirectional"))
      (node (ref "U1") (pin "P25") (pinfunction "IO_L23P_6_P25") (pintype "bidirectional"))
    )
    (net (code "140") (name "Net-(U$6-DQ1)") (class "Default")
      (node (ref "U$6") (pin "P22") (pinfunction "DQ1_P22") (pintype "bidirectional"))
      (node (ref "U1") (pin "P26") (pinfunction "IO_L23N_6_P26") (pintype "bidirectional"))
    )
    (net (code "141") (name "Net-(U$6-DQ2)") (class "Default")
      (node (ref "U$6") (pin "P23") (pinfunction "DQ2_P23") (pintype "bidirectional"))
      (node (ref "U1") (pin "P27") (pinfunction "IO_L22P_6_P27") (pintype "bidirectional"))
    )
    (net (code "142") (name "Net-(U$6-DQ3)") (class "Default")
      (node (ref "U$6") (pin "P25") (pinfunction "DQ3_P25") (pintype "bidirectional"))
      (node (ref "U1") (pin "P28") (pinfunction "IO_L22N_6_P28") (pintype "bidirectional"))
    )
    (net (code "143") (name "Net-(U$6-DQ4)") (class "Default")
      (node (ref "U$6") (pin "P26") (pinfunction "DQ4_P26") (pintype "bidirectional"))
      (node (ref "U1") (pin "P30") (pinfunction "IO_L21P_6_P30") (pintype "bidirectional"))
    )
    (net (code "144") (name "Net-(U$6-DQ5)") (class "Default")
      (node (ref "U$6") (pin "P27") (pinfunction "DQ5_P27") (pintype "bidirectional"))
      (node (ref "U1") (pin "P31") (pinfunction "IO_L21N_6_P31") (pintype "bidirectional"))
    )
    (net (code "145") (name "Net-(U$6-DQ6)") (class "Default")
      (node (ref "U$6") (pin "P28") (pinfunction "DQ6_P28") (pintype "bidirectional"))
      (node (ref "U1") (pin "P32") (pinfunction "IO_L20P_6_P32") (pintype "bidirectional"))
    )
    (net (code "146") (name "Net-(U$6-DQ7)") (class "Default")
      (node (ref "U$6") (pin "P29") (pinfunction "DQ7_P29") (pintype "bidirectional"))
      (node (ref "U1") (pin "P33") (pinfunction "IO_L20N_6_P33") (pintype "bidirectional"))
    )
    (net (code "147") (name "Net-(U$6-OE)") (class "Default")
      (node (ref "U$6") (pin "P32") (pinfunction "OE_P32") (pintype "bidirectional"))
      (node (ref "U1") (pin "P36") (pinfunction "IO_L01N_6VRP_6_P36") (pintype "bidirectional"))
    )
    (net (code "148") (name "Net-(U$6-WE)") (class "Default")
      (node (ref "U$6") (pin "P5") (pinfunction "WE_P5") (pintype "bidirectional"))
      (node (ref "U1") (pin "P6") (pinfunction "IO_L20N_7_P6") (pintype "bidirectional"))
    )
    (net (code "149") (name "Net-(U1A-IO_L27N_0)") (class "Default")
      (node (ref "SV3") (pin "3") (pinfunction "3_3") (pintype "passive"))
      (node (ref "U1") (pin "P137") (pinfunction "IO_L27N_0_P137") (pintype "bidirectional"))
    )
    (net (code "150") (name "Net-(U1A-IO_L27P_0)") (class "Default")
      (node (ref "SV3") (pin "4") (pinfunction "4_4") (pintype "passive"))
      (node (ref "U1") (pin "P135") (pinfunction "IO_L27P_0_P135") (pintype "bidirectional"))
    )
    (net (code "151") (name "Net-(U1A-IO_L30N_0)") (class "Default")
      (node (ref "SV3") (pin "5") (pinfunction "5_5") (pintype "passive"))
      (node (ref "U1") (pin "P132") (pinfunction "IO_L30N_0_P132") (pintype "bidirectional"))
    )
    (net (code "152") (name "Net-(U1A-IO_L31N_0)") (class "Default")
      (node (ref "SV3") (pin "6") (pinfunction "6_6") (pintype "passive"))
      (node (ref "U1") (pin "P130") (pinfunction "IO_L31N_0_P130") (pintype "bidirectional"))
    )
    (net (code "153") (name "Net-(U1A-IO_L31P_0VREF_0)") (class "Default")
      (node (ref "SV3") (pin "7") (pinfunction "7_7") (pintype "passive"))
      (node (ref "U1") (pin "P129") (pinfunction "IO_L31P_0VREF_0_P129") (pintype "bidirectional"))
    )
    (net (code "154") (name "Net-(U1A-IO_L32N_0GCLK7)") (class "Default")
      (node (ref "SV3") (pin "8") (pinfunction "8_8") (pintype "passive"))
      (node (ref "U1") (pin "P128") (pinfunction "IO_L32N_0GCLK7_P128") (pintype "bidirectional"))
    )
    (net (code "155") (name "Net-(U1A-IO_L32P_0GCLK6)") (class "Default")
      (node (ref "SV3") (pin "9") (pinfunction "9_9") (pintype "passive"))
      (node (ref "U1") (pin "P127") (pinfunction "IO_L32P_0GCLK6_P127") (pintype "bidirectional"))
    )
    (net (code "156") (name "Net-(U1C-IO_L31N_1VREF_1)") (class "Default")
      (node (ref "SV3") (pin "10") (pinfunction "10_10") (pintype "passive"))
      (node (ref "U1") (pin "P123") (pinfunction "IO_L31N_1VREF_1_P123") (pintype "bidirectional"))
    )
    (net (code "157") (name "Net-(U1N-TCK)") (class "Default")
      (node (ref "R2") (pin "1") (pinfunction "1_1") (pintype "passive"))
      (node (ref "U1") (pin "P110") (pinfunction "TCK_P110") (pintype "bidirectional"))
    )
    (net (code "158") (name "Net-(U1N-TDI)") (class "Default")
      (node (ref "R1") (pin "1") (pinfunction "1_1") (pintype "passive"))
      (node (ref "U1") (pin "P144") (pinfunction "TDI_P144") (pintype "bidirectional"))
    )
    (net (code "159") (name "Net-(U1N-TMS)") (class "Default")
      (node (ref "R3") (pin "1") (pinfunction "1_1") (pintype "passive"))
      (node (ref "U1") (pin "P111") (pinfunction "TMS_P111") (pintype "bidirectional"))
    )
    (net (code "160") (name "unconnected-(IC1-NC.1-Pad2)") (class "Default")
      (node (ref "IC1") (pin "2") (pinfunction "NC.1_2") (pintype "bidirectional"))
    )
    (net (code "161") (name "unconnected-(IC1-NC.2-Pad9)") (class "Default")
      (node (ref "IC1") (pin "9") (pinfunction "NC.2_9") (pintype "bidirectional"))
    )
    (net (code "162") (name "unconnected-(IC1-NC.3-Pad12)") (class "Default")
      (node (ref "IC1") (pin "12") (pinfunction "NC.3_12") (pintype "bidirectional"))
    )
    (net (code "163") (name "unconnected-(IC1-NC.4-Pad14)") (class "Default")
      (node (ref "IC1") (pin "14") (pinfunction "NC.4_14") (pintype "bidirectional"))
    )
    (net (code "164") (name "unconnected-(IC1-NC.5-Pad15)") (class "Default")
      (node (ref "IC1") (pin "15") (pinfunction "NC.5_15") (pintype "bidirectional"))
    )
    (net (code "165") (name "unconnected-(IC1-NC.6-Pad16)") (class "Default")
      (node (ref "IC1") (pin "16") (pinfunction "NC.6_16") (pintype "bidirectional"))
    )
    (net (code "166") (name "unconnected-(IC1-{slash}CEO-Pad13)") (class "Default")
      (node (ref "IC1") (pin "13") (pinfunction "/CEO_13") (pintype "bidirectional"))
    )
    (net (code "167") (name "unconnected-(REG1.2-VOUT2-Pad2)") (class "Default")
      (node (ref "REG1.2") (pin "2") (pinfunction "VOUT2_2") (pintype "bidirectional"))
    )
    (net (code "168") (name "unconnected-(REG2.5-VOUT2-Pad2)") (class "Default")
      (node (ref "REG2.5") (pin "2") (pinfunction "VOUT2_2") (pintype "bidirectional"))
    )
    (net (code "169") (name "unconnected-(U$2-TRI-PadENA)") (class "Default")
      (node (ref "U$2") (pin "ENA") (pinfunction "TRI_ENA") (pintype "input"))
    )
    (net (code "170") (name "unconnected-(U$3-CARD_DETECT-PadCD)") (class "Default")
      (node (ref "U$3") (pin "CD") (pinfunction "CARD_DETECT_CD") (pintype "passive"))
    )
    (net (code "171") (name "unconnected-(U$3-DAT1-Pad8)") (class "Default")
      (node (ref "U$3") (pin "8") (pinfunction "DAT1_8") (pintype "bidirectional"))
    )
    (net (code "172") (name "unconnected-(U$3-DAT2-Pad9)") (class "Default")
      (node (ref "U$3") (pin "9") (pinfunction "DAT2_9") (pintype "bidirectional"))
    )
    (net (code "173") (name "unconnected-(U$3-WRITE_PROTECT-PadWP)") (class "Default")
      (node (ref "U$3") (pin "WP") (pinfunction "WRITE_PROTECT_WP") (pintype "passive"))
    )
    (net (code "174") (name "unconnected-(U$4-VOUT2-Pad2)") (class "Default")
      (node (ref "U$4") (pin "2") (pinfunction "VOUT2_2") (pintype "bidirectional"))
    )
    (net (code "175") (name "unconnected-(U1N-HSWAP_EN-PadP142)") (class "Default")
      (node (ref "U1") (pin "P142") (pinfunction "HSWAP_EN_P142") (pintype "bidirectional"))
    )
    (net (code "176") (name "unconnected-(X1-Pad10)") (class "Default")
      (node (ref "X1") (pin "10") (pinfunction "10_10") (pintype "passive"))
    )
    (net (code "177") (name "unconnected-(X1-Pad12)") (class "Default")
      (node (ref "X1") (pin "12") (pinfunction "12_12") (pintype "passive"))
    )
    (net (code "178") (name "unconnected-(X3-Pad2)") (class "Default")
      (node (ref "X3") (pin "2") (pinfunction "2_2") (pintype "passive"))
    )
    (net (code "179") (name "unconnected-(X3-Pad8)") (class "Default")
      (node (ref "X3") (pin "8") (pinfunction "8_8") (pintype "passive"))
    )
    (net (code "180") (name "unconnected-(X4-PadG2)") (class "Default")
      (node (ref "X4") (pin "G2") (pinfunction "G2_G2") (pintype "passive"))
    )
    (net (code "181") (name "unconnected-(X5-PadG2)") (class "Default")
      (node (ref "X5") (pin "G2") (pinfunction "G2_G2") (pintype "passive"))
    )
    (net (code "182") (name "unconnected-(X6-Pad1)") (class "Default")
      (node (ref "X6") (pin "1") (pinfunction "1_1") (pintype "passive"))
    )
  )
)
